# CESC16_copy.net
KiCad netlist of a schematic drawn in EasyEDA
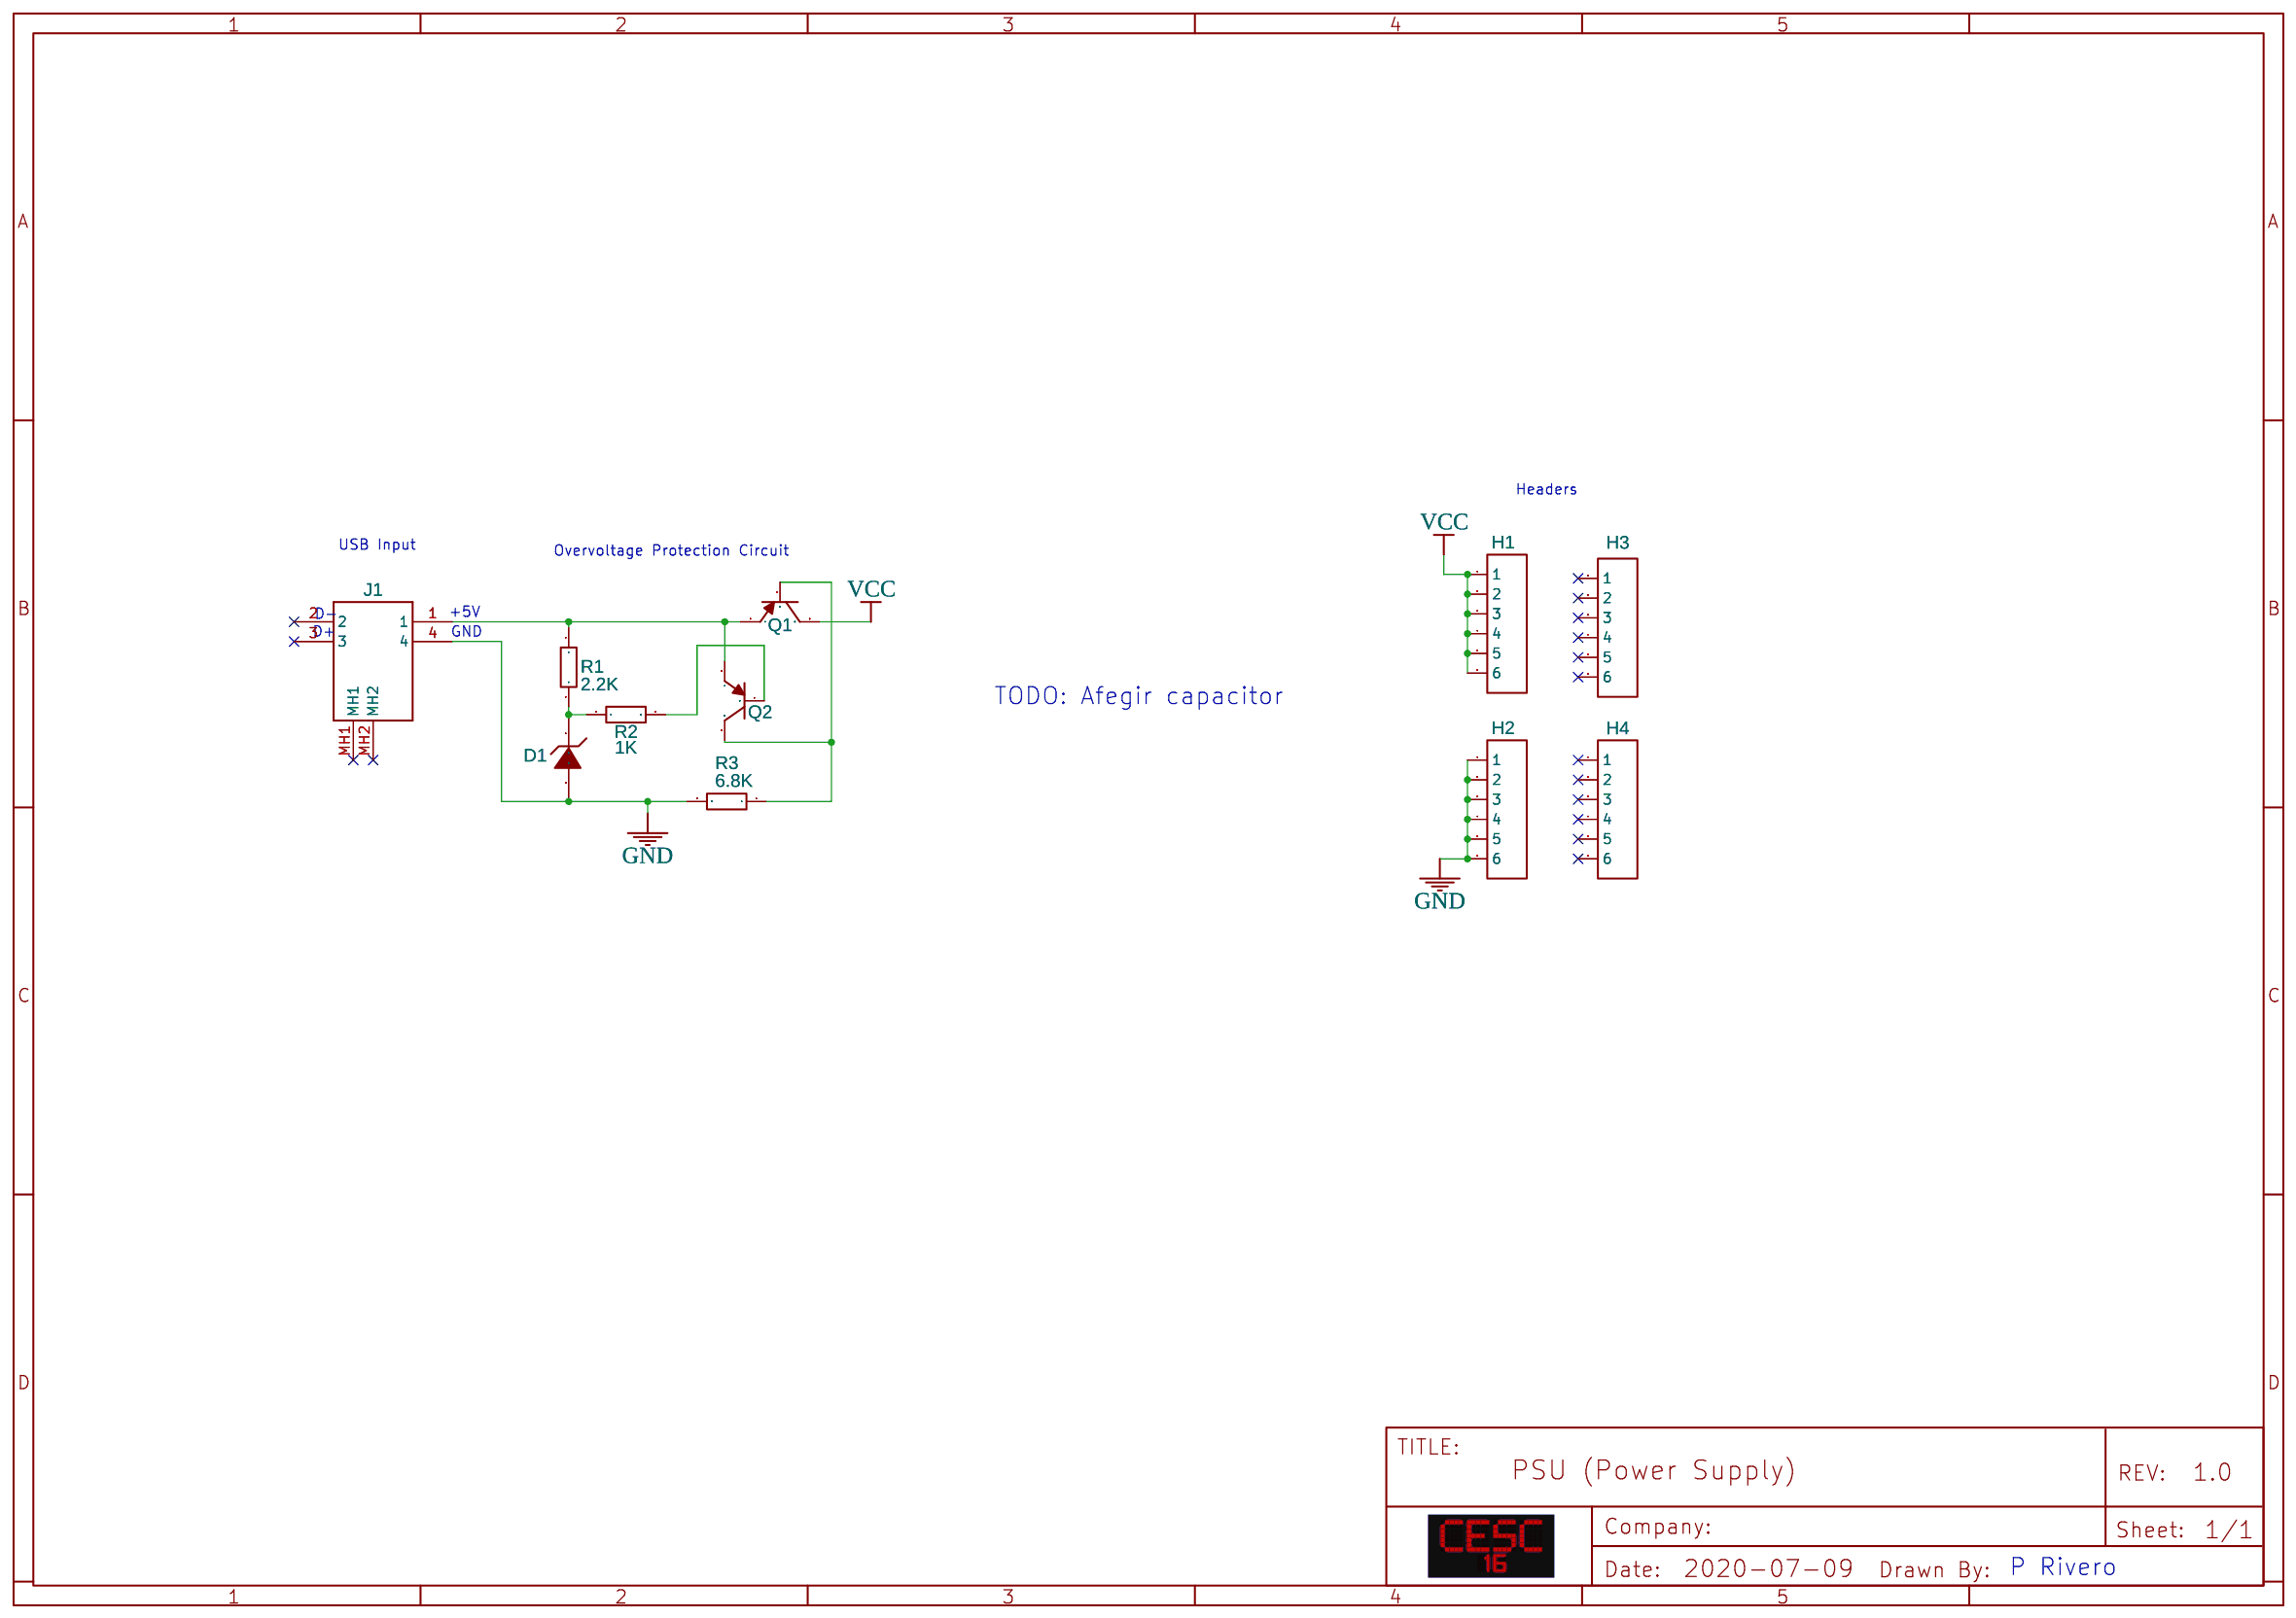
[diagram p0: PSU]
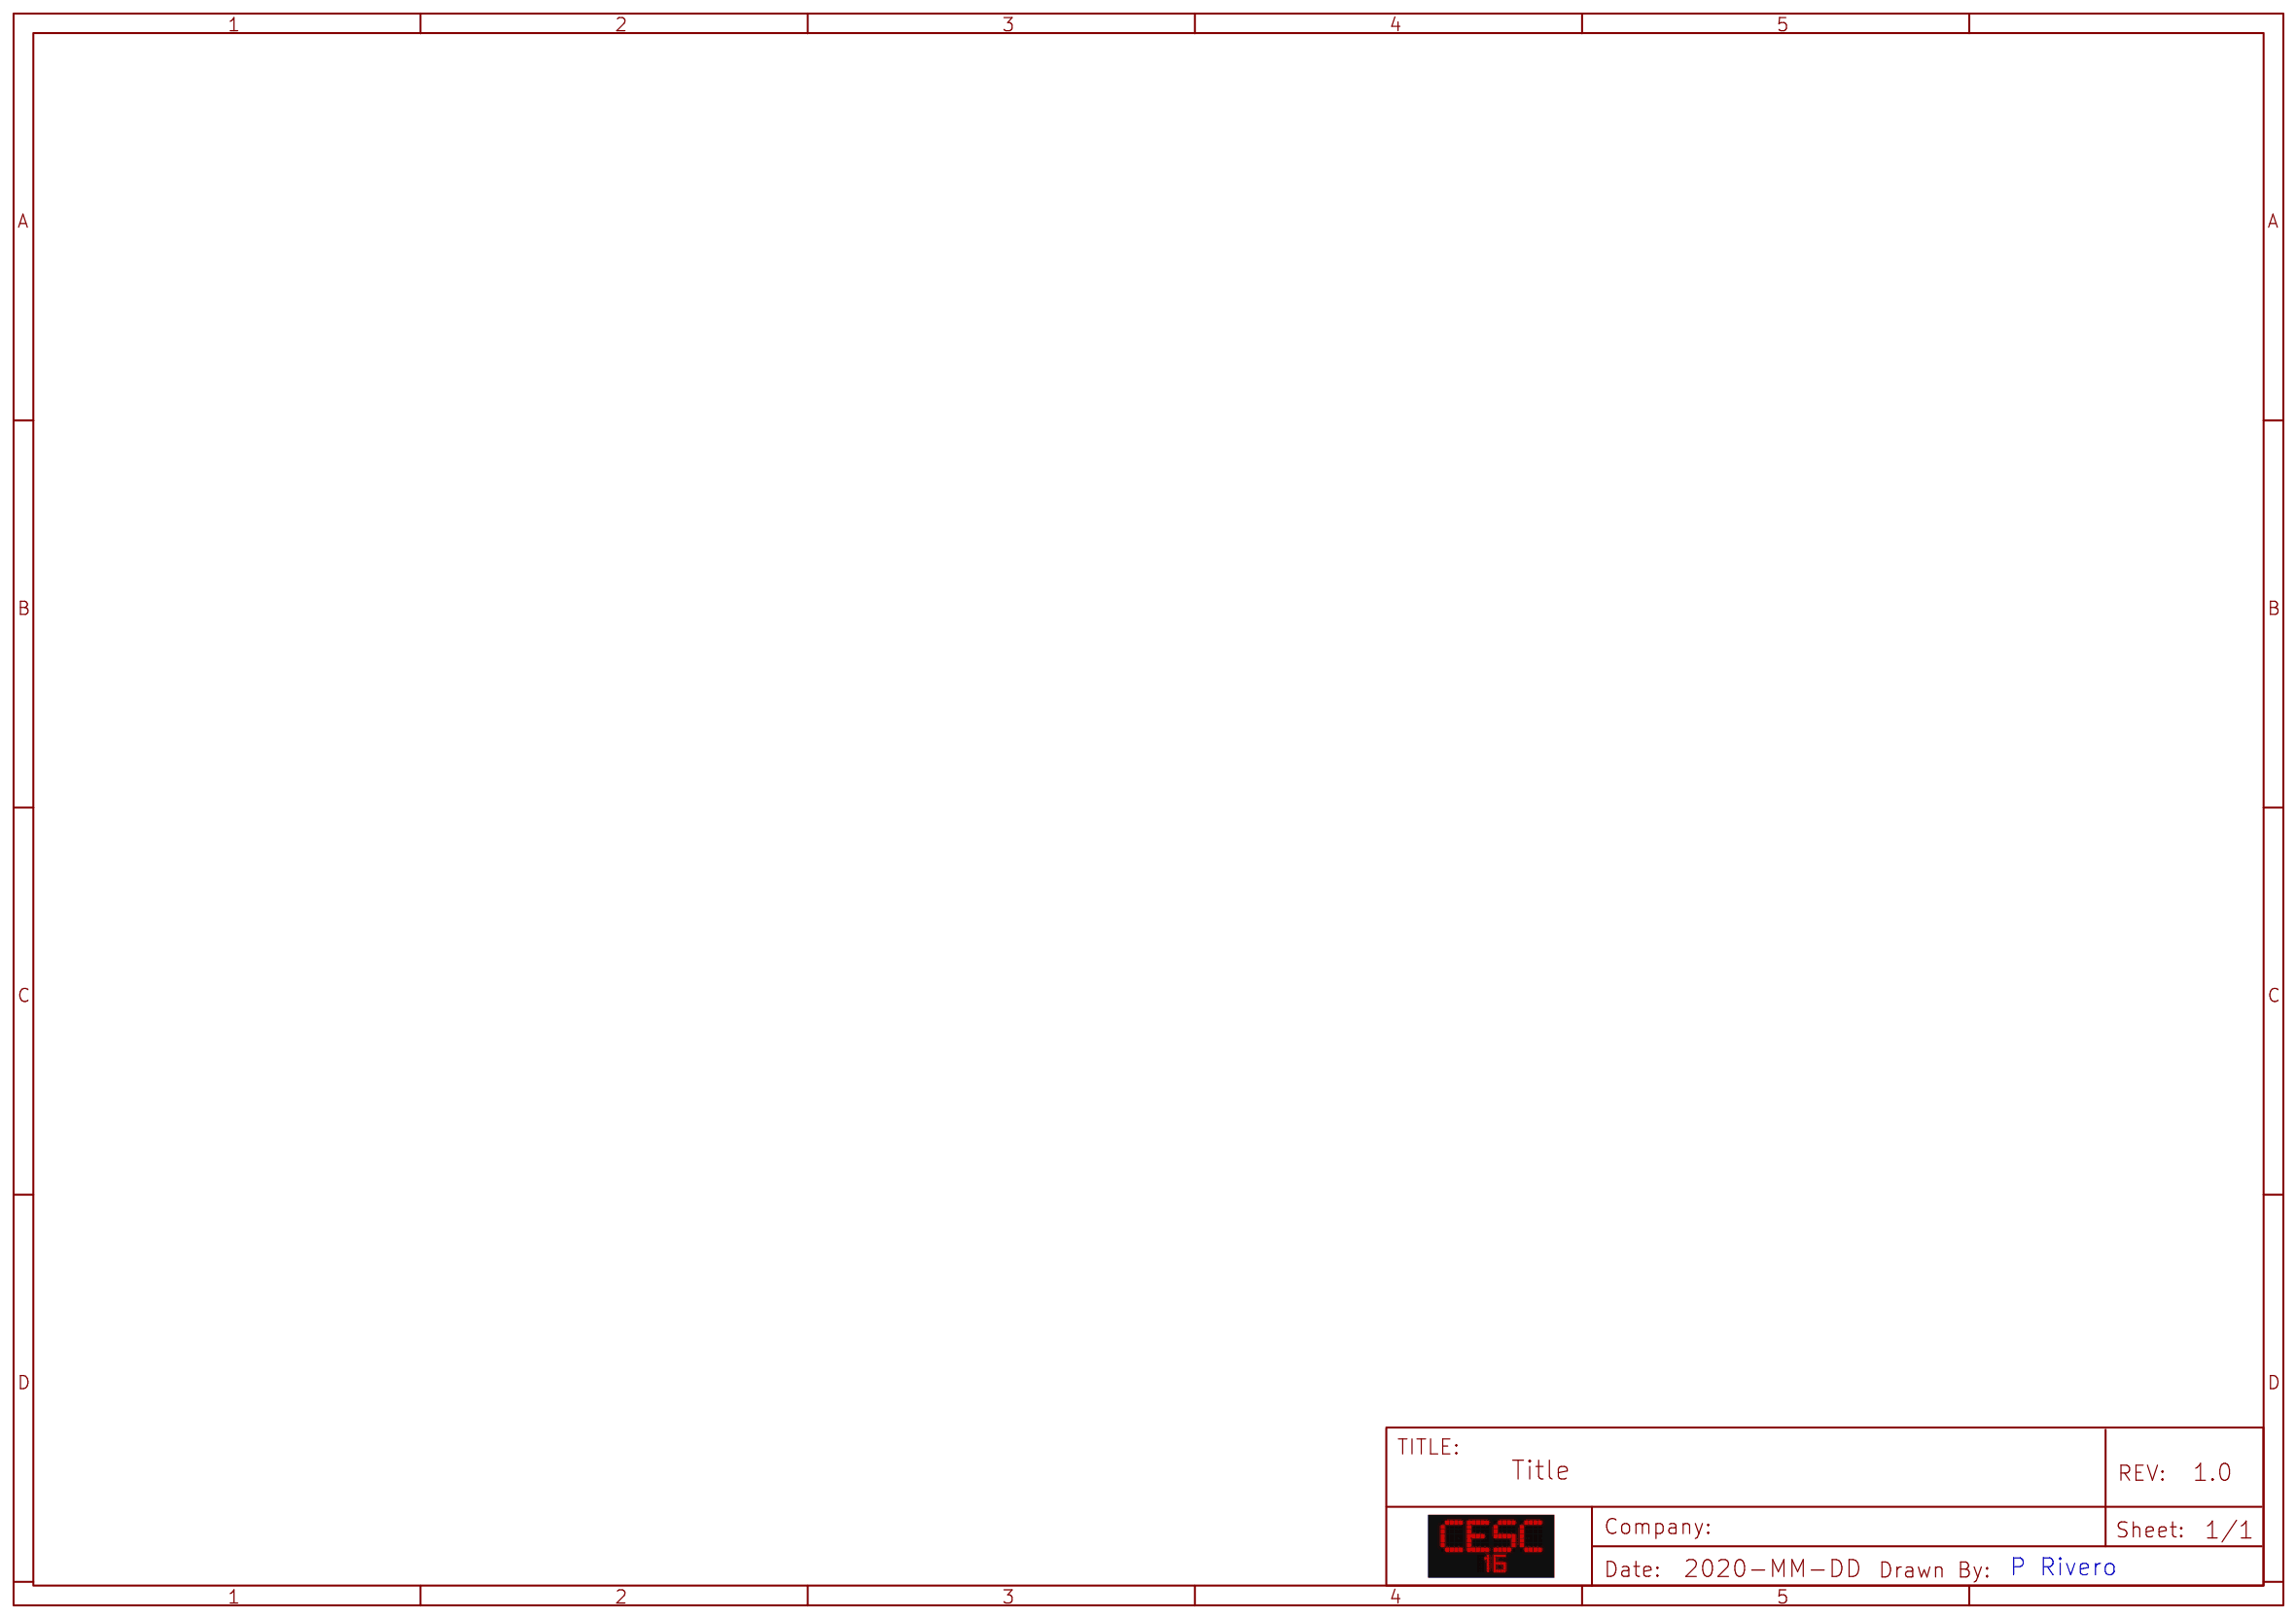
[diagram p1: _Template]
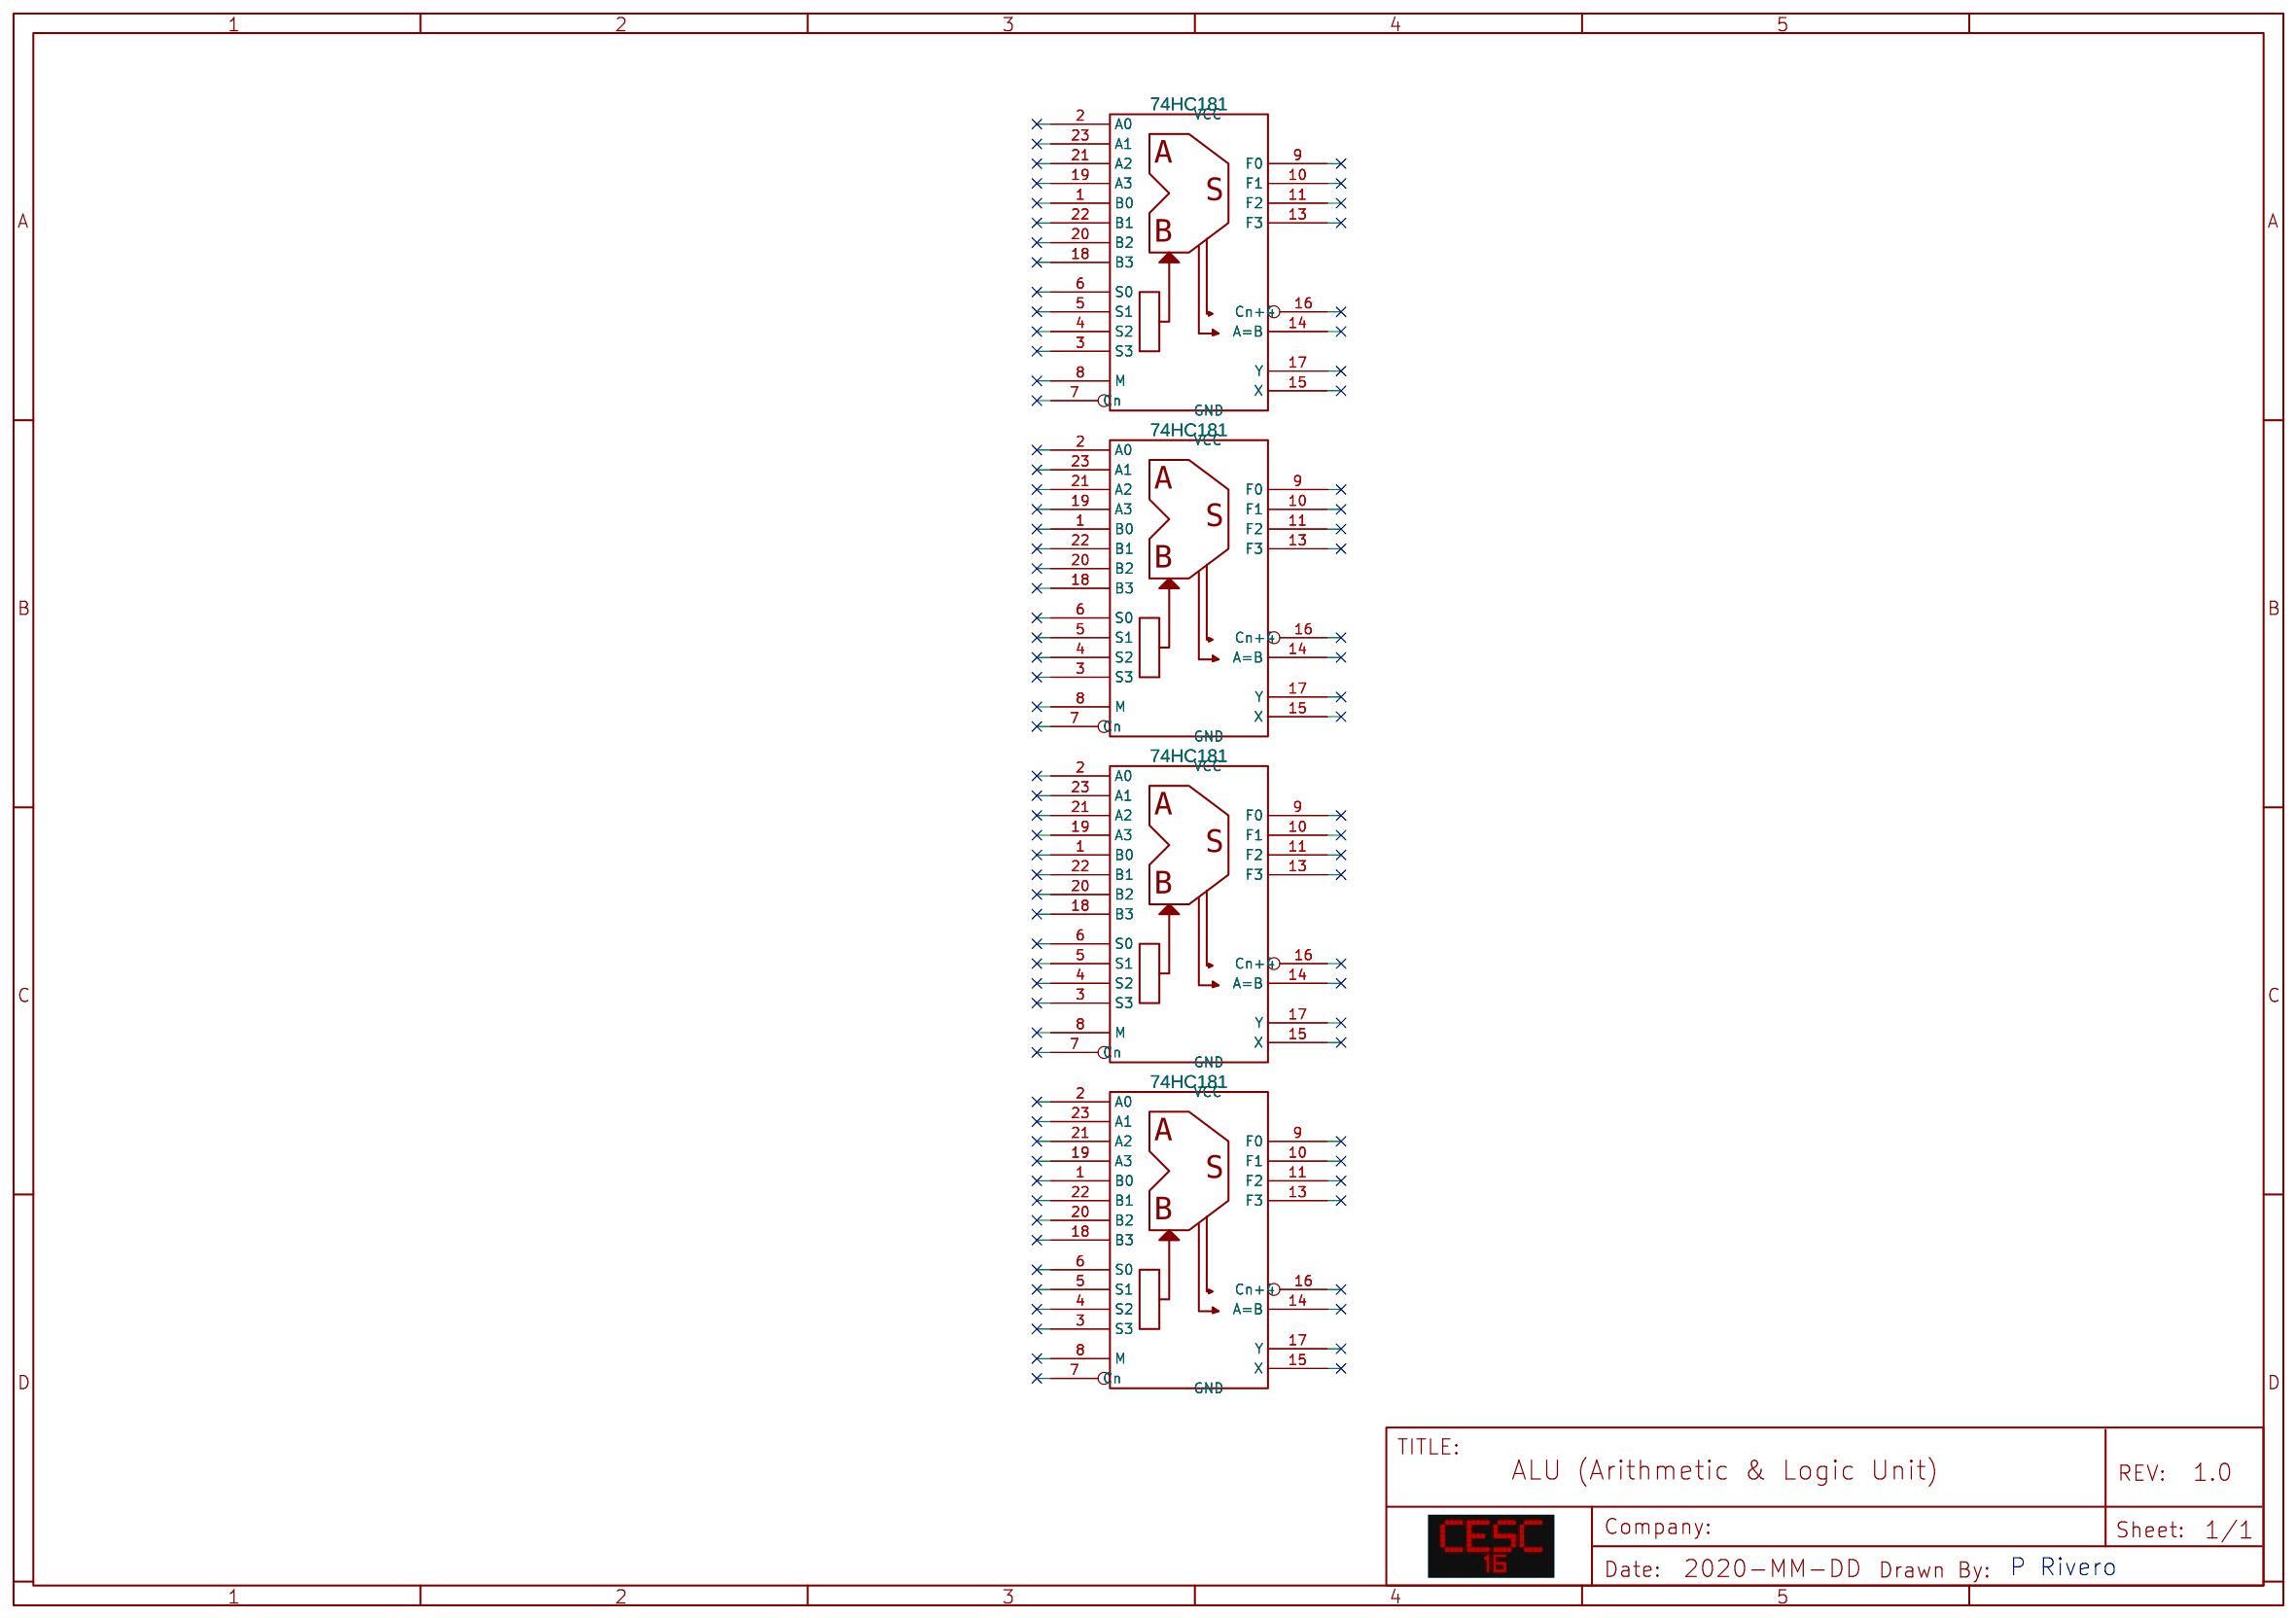
[diagram p2: ALU]
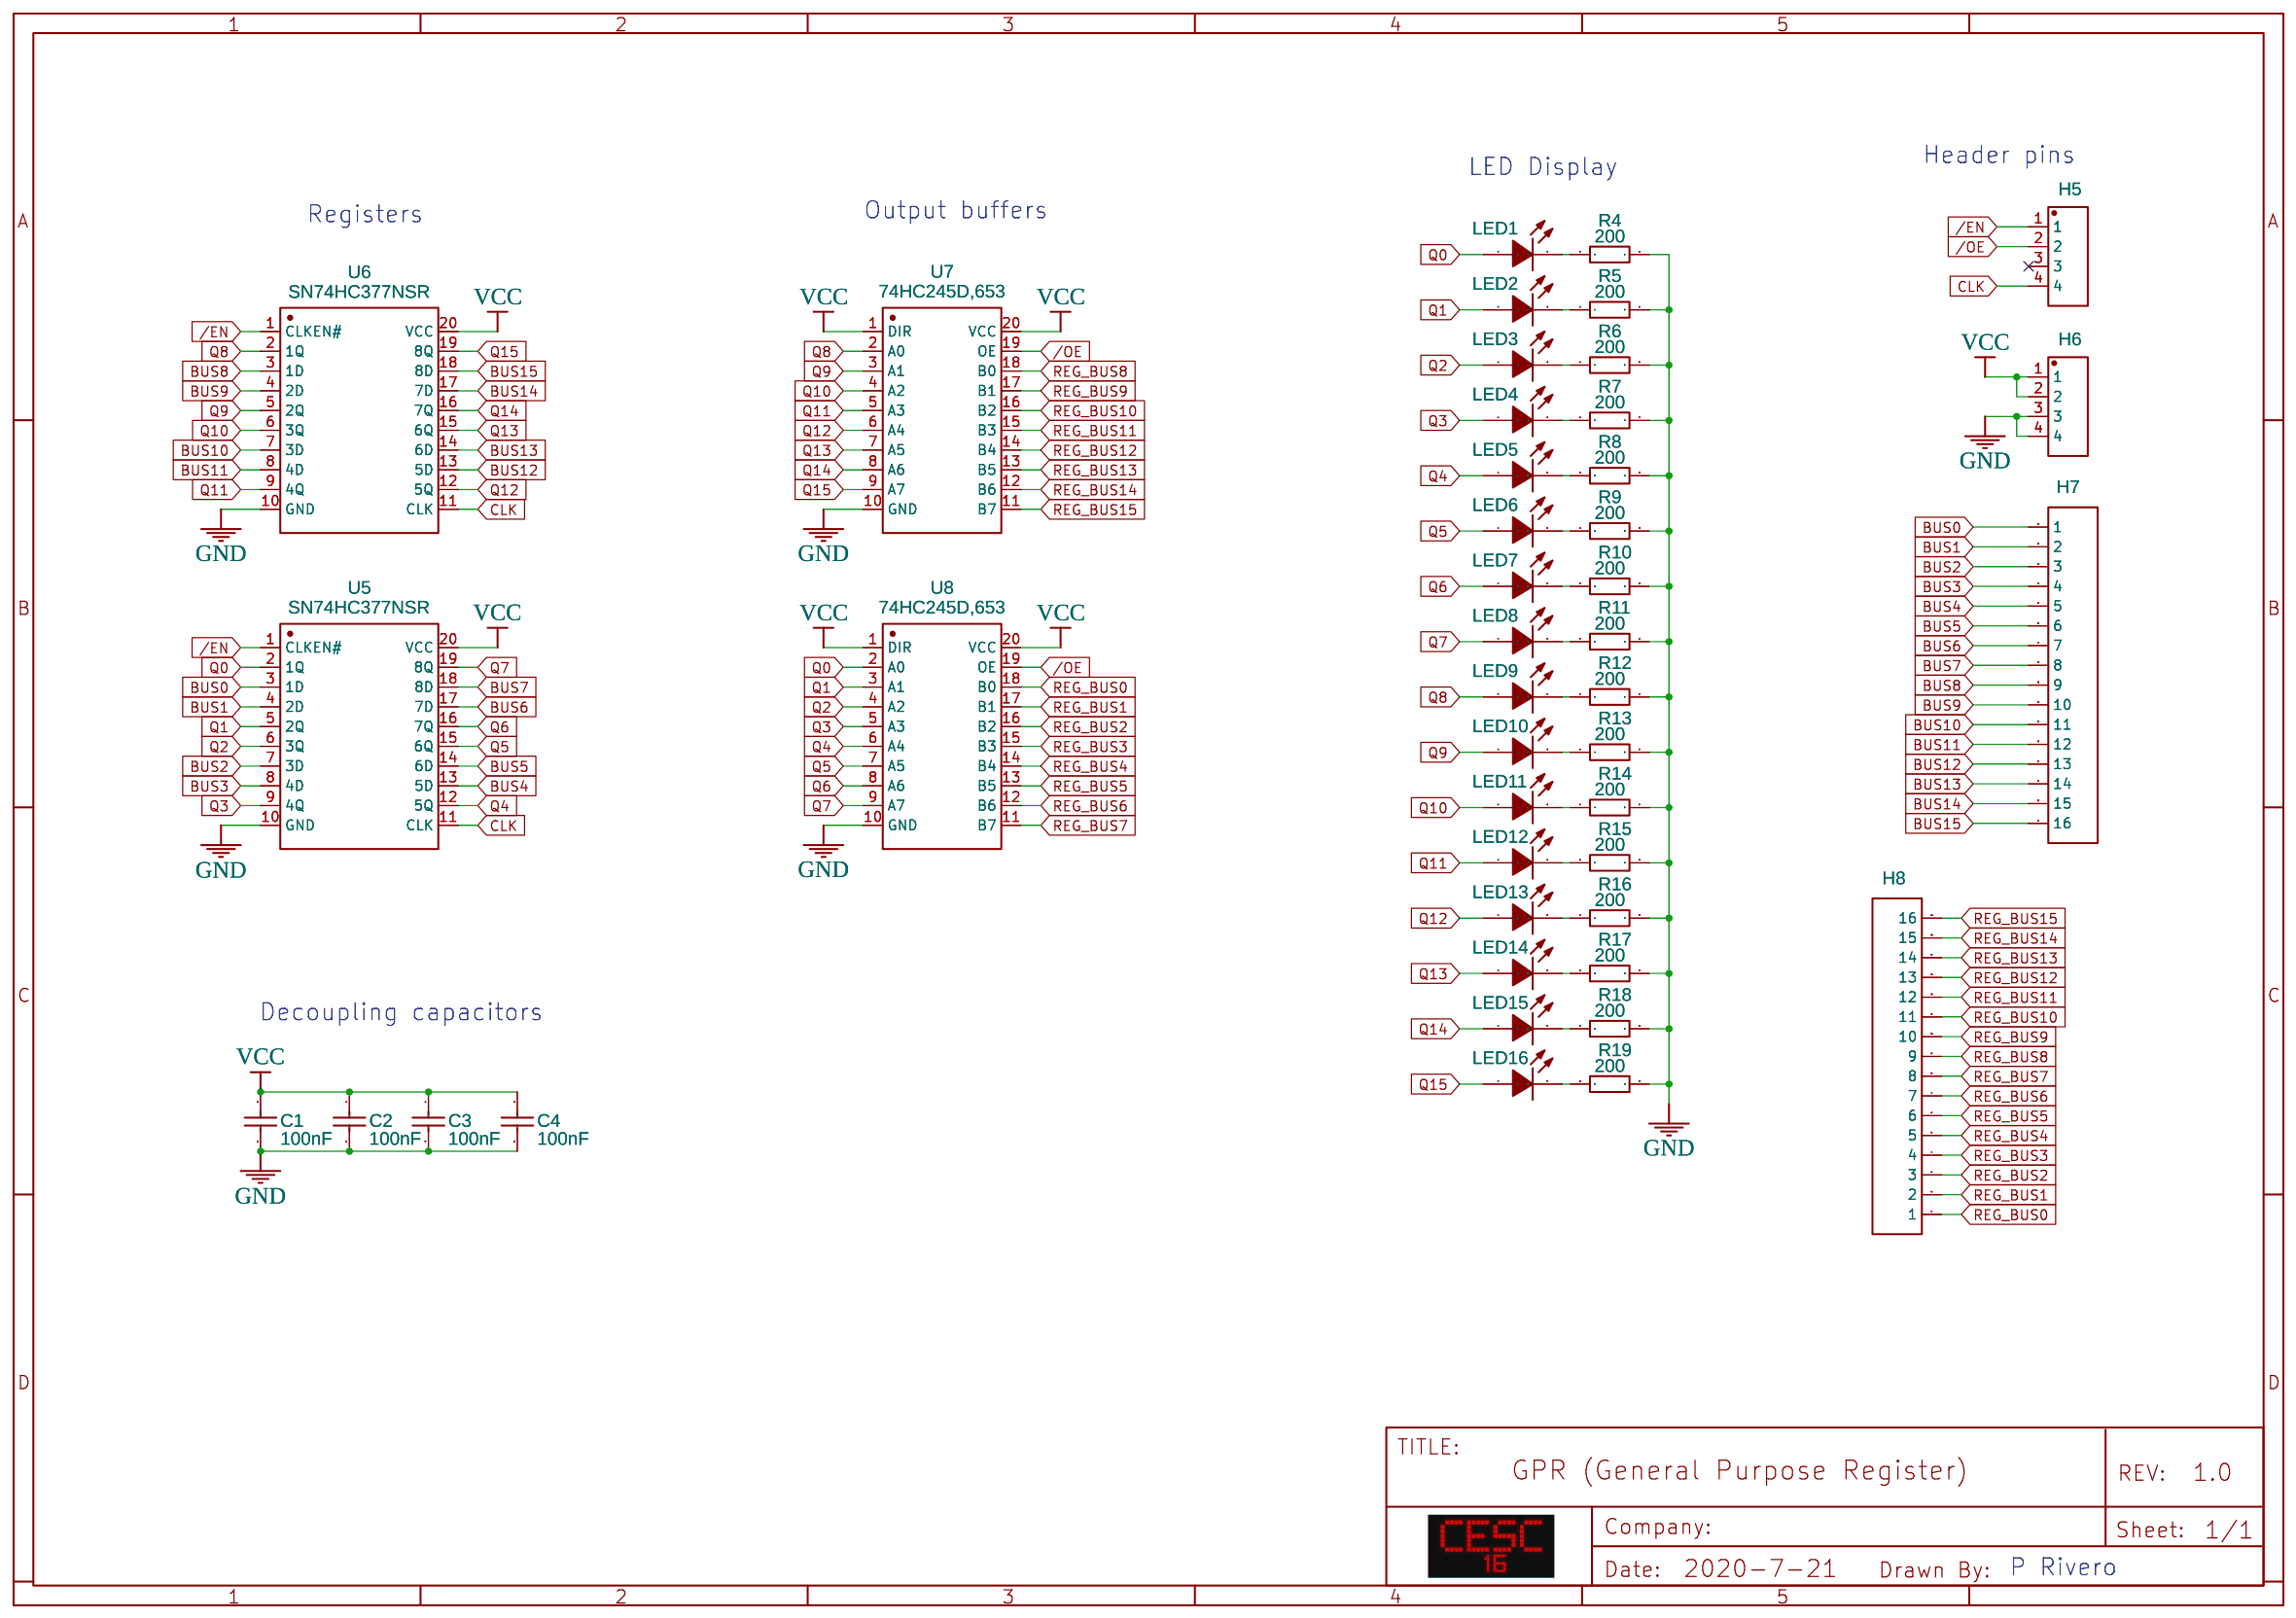
[diagram p3: GPR]

(export (version "E")
  (design (tool "Eeschema 10.0.6"))
  (components
    (comp (ref "D1")
      (value "ZMM5V6")
      (fields (field (name "BOM_Supplier Part") "C8062"))
      (libsource (lib "") (part "ZMM5V6"))
    )
    (comp (ref "H1")
      (value "Header-Male-2.54_1x6")
      (fields (field (name "BOM_Supplier Part") "C37208"))
      (libsource (lib "") (part "Header-Male-2.54_1x6"))
    )
    (comp (ref "H2")
      (value "Header-Male-2.54_1x6")
      (fields (field (name "BOM_Supplier Part") "C37208"))
      (libsource (lib "") (part "Header-Male-2.54_1x6"))
    )
    (comp (ref "H3")
      (value "Header-Male-2.54_1x6")
      (fields (field (name "BOM_Supplier Part") "C37208"))
      (libsource (lib "") (part "Header-Male-2.54_1x6"))
    )
    (comp (ref "H4")
      (value "Header-Male-2.54_1x6")
      (fields (field (name "BOM_Supplier Part") "C37208"))
      (libsource (lib "") (part "Header-Male-2.54_1x6"))
    )
    (comp (ref "J1") (value "UJ2-BH-1-TH") (libsource (lib "") (part "UJ2-BH-1-TH")))
    (comp (ref "Q1")
      (value "S9012 2T1")
      (fields (field (name "BOM_Supplier Part") "C8543"))
      (libsource (lib "") (part "S9012 2T1"))
    )
    (comp (ref "Q2")
      (value "S9012 2T1")
      (fields (field (name "BOM_Supplier Part") "C8543"))
      (libsource (lib "") (part "S9012 2T1_1"))
    )
    (comp (ref "R1")
      (value "2.2K")
      (fields
        (field (name "BOM_Manufacturer Part") "0603WAF2201T5E")
        (field (name "BOM_Supplier Part") "C4190")
      )
      (libsource (lib "") (part "0603WAF2201T5E"))
    )
    (comp (ref "R2")
      (value "1K")
      (fields
        (field (name "BOM_Manufacturer Part") "0402WGF1001TCE")
        (field (name "BOM_Supplier Part") "C11702")
      )
      (libsource (lib "") (part "0402WGF1001TCE"))
    )
    (comp (ref "R3")
      (value "6.8K")
      (fields
        (field (name "BOM_Manufacturer Part") "0402WGF6801TCE")
        (field (name "BOM_Supplier Part") "C25917")
      )
      (libsource (lib "") (part "0402WGF6801TCE"))
    )
    (comp (ref "U1") (value "74HC181") (libsource (lib "") (part "74LS181")))
    (comp (ref "U2") (value "74HC181") (libsource (lib "") (part "74LS181")))
    (comp (ref "U3") (value "74HC181") (libsource (lib "") (part "74LS181")))
    (comp (ref "U4") (value "74HC181") (libsource (lib "") (part "74LS181")))
    (comp (ref "C1")
      (value "100nF")
      (fields
        (field (name "BOM_Manufacturer Part") "CL05B104KO5NNNC")
        (field (name "BOM_Supplier Part") "C1525")
      )
      (libsource (lib "") (part "CL05B104KO5NNNC"))
    )
    (comp (ref "C2")
      (value "100nF")
      (fields
        (field (name "BOM_Manufacturer Part") "CL05B104KO5NNNC")
        (field (name "BOM_Supplier Part") "C1525")
      )
      (libsource (lib "") (part "CL05B104KO5NNNC"))
    )
    (comp (ref "C3")
      (value "100nF")
      (fields
        (field (name "BOM_Manufacturer Part") "CL05B104KO5NNNC")
        (field (name "BOM_Supplier Part") "C1525")
      )
      (libsource (lib "") (part "CL05B104KO5NNNC"))
    )
    (comp (ref "C4")
      (value "100nF")
      (fields
        (field (name "BOM_Manufacturer Part") "CL05B104KO5NNNC")
        (field (name "BOM_Supplier Part") "C1525")
      )
      (libsource (lib "") (part "CL05B104KO5NNNC"))
    )
    (comp (ref "H5")
      (value "Header-Male-2.54_1x4_C59481")
      (fields
        (field (name "BOM_Manufacturer Part") "Headers  Pins 1*4P")
        (field (name "BOM_Supplier Part") "C59481")
      )
      (libsource (lib "") (part "Header-Male-2.54_1x4_C59481"))
    )
    (comp (ref "H6")
      (value "Header-Male-2.54_1x4_C59481")
      (fields
        (field (name "BOM_Manufacturer Part") "Headers  Pins 1*4P")
        (field (name "BOM_Supplier Part") "C59481")
      )
      (libsource (lib "") (part "Header-Male-2.54_1x4_C59481"))
    )
    (comp (ref "H7")
      (value "Header-Female-2.54_1x16")
      (fields
        (field (name "BOM_Manufacturer Part") "Female header1*16P pitch 2.54mm")
        (field (name "BOM_Supplier Part") "C66987")
      )
      (libsource (lib "") (part "Header-Female-2.54_1x16_1"))
    )
    (comp (ref "H8")
      (value "Header-Female-2.54_1x16")
      (fields
        (field (name "BOM_Manufacturer Part") "Female header1*16P pitch 2.54mm")
        (field (name "BOM_Supplier Part") "C66987")
      )
      (libsource (lib "") (part "Header-Female-2.54_1x16"))
    )
    (comp (ref "LED1")
      (value "KT-0603R")
      (fields (field (name "BOM_Supplier Part") "C2286"))
      (libsource (lib "") (part "KT-0603R"))
    )
    (comp (ref "LED2")
      (value "KT-0603R")
      (fields (field (name "BOM_Supplier Part") "C2286"))
      (libsource (lib "") (part "KT-0603R"))
    )
    (comp (ref "LED3")
      (value "KT-0603R")
      (fields (field (name "BOM_Supplier Part") "C2286"))
      (libsource (lib "") (part "KT-0603R"))
    )
    (comp (ref "LED4")
      (value "KT-0603R")
      (fields (field (name "BOM_Supplier Part") "C2286"))
      (libsource (lib "") (part "KT-0603R"))
    )
    (comp (ref "LED5")
      (value "KT-0603R")
      (fields (field (name "BOM_Supplier Part") "C2286"))
      (libsource (lib "") (part "KT-0603R"))
    )
    (comp (ref "LED6")
      (value "KT-0603R")
      (fields (field (name "BOM_Supplier Part") "C2286"))
      (libsource (lib "") (part "KT-0603R"))
    )
    (comp (ref "LED7")
      (value "KT-0603R")
      (fields (field (name "BOM_Supplier Part") "C2286"))
      (libsource (lib "") (part "KT-0603R"))
    )
    (comp (ref "LED8")
      (value "KT-0603R")
      (fields (field (name "BOM_Supplier Part") "C2286"))
      (libsource (lib "") (part "KT-0603R"))
    )
    (comp (ref "LED9")
      (value "KT-0603R")
      (fields (field (name "BOM_Supplier Part") "C2286"))
      (libsource (lib "") (part "KT-0603R"))
    )
    (comp (ref "LED10")
      (value "KT-0603R")
      (fields (field (name "BOM_Supplier Part") "C2286"))
      (libsource (lib "") (part "KT-0603R"))
    )
    (comp (ref "LED11")
      (value "KT-0603R")
      (fields (field (name "BOM_Supplier Part") "C2286"))
      (libsource (lib "") (part "KT-0603R"))
    )
    (comp (ref "LED12")
      (value "KT-0603R")
      (fields (field (name "BOM_Supplier Part") "C2286"))
      (libsource (lib "") (part "KT-0603R"))
    )
    (comp (ref "LED13")
      (value "KT-0603R")
      (fields (field (name "BOM_Supplier Part") "C2286"))
      (libsource (lib "") (part "KT-0603R"))
    )
    (comp (ref "LED14")
      (value "KT-0603R")
      (fields (field (name "BOM_Supplier Part") "C2286"))
      (libsource (lib "") (part "KT-0603R"))
    )
    (comp (ref "LED15")
      (value "KT-0603R")
      (fields (field (name "BOM_Supplier Part") "C2286"))
      (libsource (lib "") (part "KT-0603R"))
    )
    (comp (ref "LED16")
      (value "KT-0603R")
      (fields (field (name "BOM_Supplier Part") "C2286"))
      (libsource (lib "") (part "KT-0603R"))
    )
    (comp (ref "R4")
      (value "200")
      (fields
        (field (name "BOM_Manufacturer Part") "0603WAF2000T5E")
        (field (name "BOM_Supplier Part") "C8218")
      )
      (libsource (lib "") (part "0603WAF2000T5E"))
    )
    (comp (ref "R5")
      (value "200")
      (fields
        (field (name "BOM_Manufacturer Part") "0603WAF2000T5E")
        (field (name "BOM_Supplier Part") "C8218")
      )
      (libsource (lib "") (part "0603WAF2000T5E"))
    )
    (comp (ref "R6")
      (value "200")
      (fields
        (field (name "BOM_Manufacturer Part") "0603WAF2000T5E")
        (field (name "BOM_Supplier Part") "C8218")
      )
      (libsource (lib "") (part "0603WAF2000T5E"))
    )
    (comp (ref "R7")
      (value "200")
      (fields
        (field (name "BOM_Manufacturer Part") "0603WAF2000T5E")
        (field (name "BOM_Supplier Part") "C8218")
      )
      (libsource (lib "") (part "0603WAF2000T5E"))
    )
    (comp (ref "R8")
      (value "200")
      (fields
        (field (name "BOM_Manufacturer Part") "0603WAF2000T5E")
        (field (name "BOM_Supplier Part") "C8218")
      )
      (libsource (lib "") (part "0603WAF2000T5E"))
    )
    (comp (ref "R9")
      (value "200")
      (fields
        (field (name "BOM_Manufacturer Part") "0603WAF2000T5E")
        (field (name "BOM_Supplier Part") "C8218")
      )
      (libsource (lib "") (part "0603WAF2000T5E"))
    )
    (comp (ref "R10")
      (value "200")
      (fields
        (field (name "BOM_Manufacturer Part") "0603WAF2000T5E")
        (field (name "BOM_Supplier Part") "C8218")
      )
      (libsource (lib "") (part "0603WAF2000T5E"))
    )
    (comp (ref "R11")
      (value "200")
      (fields
        (field (name "BOM_Manufacturer Part") "0603WAF2000T5E")
        (field (name "BOM_Supplier Part") "C8218")
      )
      (libsource (lib "") (part "0603WAF2000T5E"))
    )
    (comp (ref "R12")
      (value "200")
      (fields
        (field (name "BOM_Manufacturer Part") "0603WAF2000T5E")
        (field (name "BOM_Supplier Part") "C8218")
      )
      (libsource (lib "") (part "0603WAF2000T5E"))
    )
    (comp (ref "R13")
      (value "200")
      (fields
        (field (name "BOM_Manufacturer Part") "0603WAF2000T5E")
        (field (name "BOM_Supplier Part") "C8218")
      )
      (libsource (lib "") (part "0603WAF2000T5E"))
    )
    (comp (ref "R14")
      (value "200")
      (fields
        (field (name "BOM_Manufacturer Part") "0603WAF2000T5E")
        (field (name "BOM_Supplier Part") "C8218")
      )
      (libsource (lib "") (part "0603WAF2000T5E"))
    )
    (comp (ref "R15")
      (value "200")
      (fields
        (field (name "BOM_Manufacturer Part") "0603WAF2000T5E")
        (field (name "BOM_Supplier Part") "C8218")
      )
      (libsource (lib "") (part "0603WAF2000T5E"))
    )
    (comp (ref "R16")
      (value "200")
      (fields
        (field (name "BOM_Manufacturer Part") "0603WAF2000T5E")
        (field (name "BOM_Supplier Part") "C8218")
      )
      (libsource (lib "") (part "0603WAF2000T5E"))
    )
    (comp (ref "R17")
      (value "200")
      (fields
        (field (name "BOM_Manufacturer Part") "0603WAF2000T5E")
        (field (name "BOM_Supplier Part") "C8218")
      )
      (libsource (lib "") (part "0603WAF2000T5E"))
    )
    (comp (ref "R18")
      (value "200")
      (fields
        (field (name "BOM_Manufacturer Part") "0603WAF2000T5E")
        (field (name "BOM_Supplier Part") "C8218")
      )
      (libsource (lib "") (part "0603WAF2000T5E"))
    )
    (comp (ref "R19")
      (value "200")
      (fields
        (field (name "BOM_Manufacturer Part") "0603WAF2000T5E")
        (field (name "BOM_Supplier Part") "C8218")
      )
      (libsource (lib "") (part "0603WAF2000T5E"))
    )
    (comp (ref "U5")
      (value "SN74HC377NSR")
      (fields (field (name "BOM_Supplier Part") "C7647"))
      (libsource (lib "") (part "SN74HC377NSR"))
    )
    (comp (ref "U6")
      (value "SN74HC377NSR")
      (fields (field (name "BOM_Supplier Part") "C7647"))
      (libsource (lib "") (part "SN74HC377NSR"))
    )
    (comp (ref "U7")
      (value "74HC245D,653")
      (fields (field (name "BOM_Supplier Part") "C5625"))
      (libsource (lib "") (part "74HC245D,653"))
    )
    (comp (ref "U8")
      (value "74HC245D,653")
      (fields (field (name "BOM_Supplier Part") "C5625"))
      (libsource (lib "") (part "74HC245D,653"))
    )
  )
  (nets
    (net (code "1") (name "BUS0") (class "Default")
      (node (ref "H7") (pin "1") (pinfunction "1_1") (pintype "input"))
      (node (ref "U5") (pin "3") (pinfunction "1D_3") (pintype "unspecified"))
    )
    (net (code "2") (name "BUS1") (class "Default")
      (node (ref "H7") (pin "2") (pinfunction "2_2") (pintype "input"))
      (node (ref "U5") (pin "4") (pinfunction "2D_4") (pintype "unspecified"))
    )
    (net (code "3") (name "BUS2") (class "Default")
      (node (ref "H7") (pin "3") (pinfunction "3_3") (pintype "input"))
      (node (ref "U5") (pin "7") (pinfunction "3D_7") (pintype "unspecified"))
    )
    (net (code "4") (name "BUS3") (class "Default")
      (node (ref "H7") (pin "4") (pinfunction "4_4") (pintype "input"))
      (node (ref "U5") (pin "8") (pinfunction "4D_8") (pintype "unspecified"))
    )
    (net (code "5") (name "BUS4") (class "Default")
      (node (ref "H7") (pin "5") (pinfunction "5_5") (pintype "input"))
      (node (ref "U5") (pin "13") (pinfunction "5D_13") (pintype "unspecified"))
    )
    (net (code "6") (name "BUS5") (class "Default")
      (node (ref "H7") (pin "6") (pinfunction "6_6") (pintype "input"))
      (node (ref "U5") (pin "14") (pinfunction "6D_14") (pintype "unspecified"))
    )
    (net (code "7") (name "BUS6") (class "Default")
      (node (ref "H7") (pin "7") (pinfunction "7_7") (pintype "input"))
      (node (ref "U5") (pin "17") (pinfunction "7D_17") (pintype "unspecified"))
    )
    (net (code "8") (name "BUS7") (class "Default")
      (node (ref "H7") (pin "8") (pinfunction "8_8") (pintype "input"))
      (node (ref "U5") (pin "18") (pinfunction "8D_18") (pintype "unspecified"))
    )
    (net (code "9") (name "BUS8") (class "Default")
      (node (ref "H7") (pin "9") (pinfunction "9_9") (pintype "input"))
      (node (ref "U6") (pin "3") (pinfunction "1D_3") (pintype "unspecified"))
    )
    (net (code "10") (name "BUS9") (class "Default")
      (node (ref "H7") (pin "10") (pinfunction "10_10") (pintype "input"))
      (node (ref "U6") (pin "4") (pinfunction "2D_4") (pintype "unspecified"))
    )
    (net (code "11") (name "BUS10") (class "Default")
      (node (ref "H7") (pin "11") (pinfunction "11_11") (pintype "input"))
      (node (ref "U6") (pin "7") (pinfunction "3D_7") (pintype "unspecified"))
    )
    (net (code "12") (name "BUS11") (class "Default")
      (node (ref "H7") (pin "12") (pinfunction "12_12") (pintype "input"))
      (node (ref "U6") (pin "8") (pinfunction "4D_8") (pintype "unspecified"))
    )
    (net (code "13") (name "BUS12") (class "Default")
      (node (ref "H7") (pin "13") (pinfunction "13_13") (pintype "input"))
      (node (ref "U6") (pin "13") (pinfunction "5D_13") (pintype "unspecified"))
    )
    (net (code "14") (name "BUS13") (class "Default")
      (node (ref "H7") (pin "14") (pinfunction "14_14") (pintype "input"))
      (node (ref "U6") (pin "14") (pinfunction "6D_14") (pintype "unspecified"))
    )
    (net (code "15") (name "BUS14") (class "Default")
      (node (ref "H7") (pin "15") (pinfunction "15_15") (pintype "input"))
      (node (ref "U6") (pin "17") (pinfunction "7D_17") (pintype "unspecified"))
    )
    (net (code "16") (name "BUS15") (class "Default")
      (node (ref "H7") (pin "16") (pinfunction "16_16") (pintype "input"))
      (node (ref "U6") (pin "18") (pinfunction "8D_18") (pintype "unspecified"))
    )
    (net (code "17") (name "CLK") (class "Default")
      (node (ref "H5") (pin "4") (pinfunction "4_4") (pintype "unspecified"))
      (node (ref "U5") (pin "11") (pinfunction "CLK_11") (pintype "unspecified"))
      (node (ref "U6") (pin "11") (pinfunction "CLK_11") (pintype "unspecified"))
    )
    (net (code "18") (name "GND") (class "Default")
      (node (ref "C1") (pin "2") (pinfunction "2_2") (pintype "input"))
      (node (ref "C2") (pin "2") (pinfunction "2_2") (pintype "input"))
      (node (ref "C3") (pin "2") (pinfunction "2_2") (pintype "input"))
      (node (ref "C4") (pin "2") (pinfunction "2_2") (pintype "input"))
      (node (ref "D1") (pin "2") (pinfunction "A_2") (pintype "unspecified"))
      (node (ref "H2") (pin "1") (pinfunction "1_1") (pintype "input"))
      (node (ref "H2") (pin "2") (pinfunction "2_2") (pintype "input"))
      (node (ref "H2") (pin "3") (pinfunction "3_3") (pintype "input"))
      (node (ref "H2") (pin "4") (pinfunction "4_4") (pintype "input"))
      (node (ref "H2") (pin "5") (pinfunction "5_5") (pintype "input"))
      (node (ref "H2") (pin "6") (pinfunction "6_6") (pintype "input"))
      (node (ref "H6") (pin "3") (pinfunction "3_3") (pintype "unspecified"))
      (node (ref "H6") (pin "4") (pinfunction "4_4") (pintype "unspecified"))
      (node (ref "J1") (pin "4") (pinfunction "4_4") (pintype "bidirectional"))
      (node (ref "R10") (pin "2") (pinfunction "2_2") (pintype "input"))
      (node (ref "R11") (pin "2") (pinfunction "2_2") (pintype "input"))
      (node (ref "R12") (pin "2") (pinfunction "2_2") (pintype "input"))
      (node (ref "R13") (pin "2") (pinfunction "2_2") (pintype "input"))
      (node (ref "R14") (pin "2") (pinfunction "2_2") (pintype "input"))
      (node (ref "R15") (pin "2") (pinfunction "2_2") (pintype "input"))
      (node (ref "R16") (pin "2") (pinfunction "2_2") (pintype "input"))
      (node (ref "R17") (pin "2") (pinfunction "2_2") (pintype "input"))
      (node (ref "R18") (pin "2") (pinfunction "2_2") (pintype "input"))
      (node (ref "R19") (pin "2") (pinfunction "2_2") (pintype "input"))
      (node (ref "R3") (pin "2") (pinfunction "2_2") (pintype "input"))
      (node (ref "R4") (pin "2") (pinfunction "2_2") (pintype "input"))
      (node (ref "R5") (pin "2") (pinfunction "2_2") (pintype "input"))
      (node (ref "R6") (pin "2") (pinfunction "2_2") (pintype "input"))
      (node (ref "R7") (pin "2") (pinfunction "2_2") (pintype "input"))
      (node (ref "R8") (pin "2") (pinfunction "2_2") (pintype "input"))
      (node (ref "R9") (pin "2") (pinfunction "2_2") (pintype "input"))
      (node (ref "U5") (pin "10") (pinfunction "GND_10") (pintype "unspecified"))
      (node (ref "U6") (pin "10") (pinfunction "GND_10") (pintype "unspecified"))
      (node (ref "U7") (pin "10") (pinfunction "GND_10") (pintype "unspecified"))
      (node (ref "U8") (pin "10") (pinfunction "GND_10") (pintype "unspecified"))
    )
    (net (code "19") (name "Net-(D1-C)") (class "Default")
      (node (ref "D1") (pin "1") (pinfunction "C_1") (pintype "unspecified"))
      (node (ref "R1") (pin "2") (pinfunction "2_2") (pintype "input"))
      (node (ref "R2") (pin "1") (pinfunction "1_1") (pintype "input"))
    )
    (net (code "20") (name "Net-(LED1-K)") (class "Default")
      (node (ref "LED1") (pin "2") (pinfunction "K_2") (pintype "unspecified"))
      (node (ref "R4") (pin "1") (pinfunction "1_1") (pintype "input"))
    )
    (net (code "21") (name "Net-(LED2-K)") (class "Default")
      (node (ref "LED2") (pin "2") (pinfunction "K_2") (pintype "unspecified"))
      (node (ref "R5") (pin "1") (pinfunction "1_1") (pintype "input"))
    )
    (net (code "22") (name "Net-(LED3-K)") (class "Default")
      (node (ref "LED3") (pin "2") (pinfunction "K_2") (pintype "unspecified"))
      (node (ref "R6") (pin "1") (pinfunction "1_1") (pintype "input"))
    )
    (net (code "23") (name "Net-(LED4-K)") (class "Default")
      (node (ref "LED4") (pin "2") (pinfunction "K_2") (pintype "unspecified"))
      (node (ref "R7") (pin "1") (pinfunction "1_1") (pintype "input"))
    )
    (net (code "24") (name "Net-(LED5-K)") (class "Default")
      (node (ref "LED5") (pin "2") (pinfunction "K_2") (pintype "unspecified"))
      (node (ref "R8") (pin "1") (pinfunction "1_1") (pintype "input"))
    )
    (net (code "25") (name "Net-(LED6-K)") (class "Default")
      (node (ref "LED6") (pin "2") (pinfunction "K_2") (pintype "unspecified"))
      (node (ref "R9") (pin "1") (pinfunction "1_1") (pintype "input"))
    )
    (net (code "26") (name "Net-(LED7-K)") (class "Default")
      (node (ref "LED7") (pin "2") (pinfunction "K_2") (pintype "unspecified"))
      (node (ref "R10") (pin "1") (pinfunction "1_1") (pintype "input"))
    )
    (net (code "27") (name "Net-(LED8-K)") (class "Default")
      (node (ref "LED8") (pin "2") (pinfunction "K_2") (pintype "unspecified"))
      (node (ref "R11") (pin "1") (pinfunction "1_1") (pintype "input"))
    )
    (net (code "28") (name "Net-(LED9-K)") (class "Default")
      (node (ref "LED9") (pin "2") (pinfunction "K_2") (pintype "unspecified"))
      (node (ref "R12") (pin "1") (pinfunction "1_1") (pintype "input"))
    )
    (net (code "29") (name "Net-(LED10-K)") (class "Default")
      (node (ref "LED10") (pin "2") (pinfunction "K_2") (pintype "unspecified"))
      (node (ref "R13") (pin "1") (pinfunction "1_1") (pintype "input"))
    )
    (net (code "30") (name "Net-(LED11-K)") (class "Default")
      (node (ref "LED11") (pin "2") (pinfunction "K_2") (pintype "unspecified"))
      (node (ref "R14") (pin "1") (pinfunction "1_1") (pintype "input"))
    )
    (net (code "31") (name "Net-(LED12-K)") (class "Default")
      (node (ref "LED12") (pin "2") (pinfunction "K_2") (pintype "unspecified"))
      (node (ref "R15") (pin "1") (pinfunction "1_1") (pintype "input"))
    )
    (net (code "32") (name "Net-(LED13-K)") (class "Default")
      (node (ref "LED13") (pin "2") (pinfunction "K_2") (pintype "unspecified"))
      (node (ref "R16") (pin "1") (pinfunction "1_1") (pintype "input"))
    )
    (net (code "33") (name "Net-(LED14-K)") (class "Default")
      (node (ref "LED14") (pin "2") (pinfunction "K_2") (pintype "unspecified"))
      (node (ref "R17") (pin "1") (pinfunction "1_1") (pintype "input"))
    )
    (net (code "34") (name "Net-(LED15-K)") (class "Default")
      (node (ref "LED15") (pin "2") (pinfunction "K_2") (pintype "unspecified"))
      (node (ref "R18") (pin "1") (pinfunction "1_1") (pintype "input"))
    )
    (net (code "35") (name "Net-(LED16-K)") (class "Default")
      (node (ref "LED16") (pin "2") (pinfunction "K_2") (pintype "unspecified"))
      (node (ref "R19") (pin "1") (pinfunction "1_1") (pintype "input"))
    )
    (net (code "36") (name "Net-(Q1-B)") (class "Default")
      (node (ref "Q1") (pin "1") (pinfunction "B_1") (pintype "unspecified"))
      (node (ref "Q2") (pin "3") (pinfunction "C_3") (pintype "unspecified"))
      (node (ref "R3") (pin "1") (pinfunction "1_1") (pintype "input"))
    )
    (net (code "37") (name "Net-(Q1-E)") (class "Default")
      (node (ref "J1") (pin "1") (pinfunction "1_1") (pintype "bidirectional"))
      (node (ref "Q1") (pin "2") (pinfunction "E_2") (pintype "unspecified"))
      (node (ref "Q2") (pin "2") (pinfunction "E_2") (pintype "unspecified"))
      (node (ref "R1") (pin "1") (pinfunction "1_1") (pintype "input"))
    )
    (net (code "38") (name "Net-(Q2-B)") (class "Default")
      (node (ref "Q2") (pin "1") (pinfunction "B_1") (pintype "unspecified"))
      (node (ref "R2") (pin "2") (pinfunction "2_2") (pintype "input"))
    )
    (net (code "39") (name "Q0") (class "Default")
      (node (ref "LED1") (pin "1") (pinfunction "A_1") (pintype "unspecified"))
      (node (ref "U5") (pin "2") (pinfunction "1Q_2") (pintype "unspecified"))
      (node (ref "U8") (pin "2") (pinfunction "A0_2") (pintype "unspecified"))
    )
    (net (code "40") (name "Q1") (class "Default")
      (node (ref "LED2") (pin "1") (pinfunction "A_1") (pintype "unspecified"))
      (node (ref "U5") (pin "5") (pinfunction "2Q_5") (pintype "unspecified"))
      (node (ref "U8") (pin "3") (pinfunction "A1_3") (pintype "unspecified"))
    )
    (net (code "41") (name "Q2") (class "Default")
      (node (ref "LED3") (pin "1") (pinfunction "A_1") (pintype "unspecified"))
      (node (ref "U5") (pin "6") (pinfunction "3Q_6") (pintype "unspecified"))
      (node (ref "U8") (pin "4") (pinfunction "A2_4") (pintype "unspecified"))
    )
    (net (code "42") (name "Q3") (class "Default")
      (node (ref "LED4") (pin "1") (pinfunction "A_1") (pintype "unspecified"))
      (node (ref "U5") (pin "9") (pinfunction "4Q_9") (pintype "unspecified"))
      (node (ref "U8") (pin "5") (pinfunction "A3_5") (pintype "unspecified"))
    )
    (net (code "43") (name "Q4") (class "Default")
      (node (ref "LED5") (pin "1") (pinfunction "A_1") (pintype "unspecified"))
      (node (ref "U5") (pin "12") (pinfunction "5Q_12") (pintype "unspecified"))
      (node (ref "U8") (pin "6") (pinfunction "A4_6") (pintype "unspecified"))
    )
    (net (code "44") (name "Q5") (class "Default")
      (node (ref "LED6") (pin "1") (pinfunction "A_1") (pintype "unspecified"))
      (node (ref "U5") (pin "15") (pinfunction "6Q_15") (pintype "unspecified"))
      (node (ref "U8") (pin "7") (pinfunction "A5_7") (pintype "unspecified"))
    )
    (net (code "45") (name "Q6") (class "Default")
      (node (ref "LED7") (pin "1") (pinfunction "A_1") (pintype "unspecified"))
      (node (ref "U5") (pin "16") (pinfunction "7Q_16") (pintype "unspecified"))
      (node (ref "U8") (pin "8") (pinfunction "A6_8") (pintype "unspecified"))
    )
    (net (code "46") (name "Q7") (class "Default")
      (node (ref "LED8") (pin "1") (pinfunction "A_1") (pintype "unspecified"))
      (node (ref "U5") (pin "19") (pinfunction "8Q_19") (pintype "unspecified"))
      (node (ref "U8") (pin "9") (pinfunction "A7_9") (pintype "unspecified"))
    )
    (net (code "47") (name "Q8") (class "Default")
      (node (ref "LED9") (pin "1") (pinfunction "A_1") (pintype "unspecified"))
      (node (ref "U6") (pin "2") (pinfunction "1Q_2") (pintype "unspecified"))
      (node (ref "U7") (pin "2") (pinfunction "A0_2") (pintype "unspecified"))
    )
    (net (code "48") (name "Q9") (class "Default")
      (node (ref "LED10") (pin "1") (pinfunction "A_1") (pintype "unspecified"))
      (node (ref "U6") (pin "5") (pinfunction "2Q_5") (pintype "unspecified"))
      (node (ref "U7") (pin "3") (pinfunction "A1_3") (pintype "unspecified"))
    )
    (net (code "49") (name "Q10") (class "Default")
      (node (ref "LED11") (pin "1") (pinfunction "A_1") (pintype "unspecified"))
      (node (ref "U6") (pin "6") (pinfunction "3Q_6") (pintype "unspecified"))
      (node (ref "U7") (pin "4") (pinfunction "A2_4") (pintype "unspecified"))
    )
    (net (code "50") (name "Q11") (class "Default")
      (node (ref "LED12") (pin "1") (pinfunction "A_1") (pintype "unspecified"))
      (node (ref "U6") (pin "9") (pinfunction "4Q_9") (pintype "unspecified"))
      (node (ref "U7") (pin "5") (pinfunction "A3_5") (pintype "unspecified"))
    )
    (net (code "51") (name "Q12") (class "Default")
      (node (ref "LED13") (pin "1") (pinfunction "A_1") (pintype "unspecified"))
      (node (ref "U6") (pin "12") (pinfunction "5Q_12") (pintype "unspecified"))
      (node (ref "U7") (pin "6") (pinfunction "A4_6") (pintype "unspecified"))
    )
    (net (code "52") (name "Q13") (class "Default")
      (node (ref "LED14") (pin "1") (pinfunction "A_1") (pintype "unspecified"))
      (node (ref "U6") (pin "15") (pinfunction "6Q_15") (pintype "unspecified"))
      (node (ref "U7") (pin "7") (pinfunction "A5_7") (pintype "unspecified"))
    )
    (net (code "53") (name "Q14") (class "Default")
      (node (ref "LED15") (pin "1") (pinfunction "A_1") (pintype "unspecified"))
      (node (ref "U6") (pin "16") (pinfunction "7Q_16") (pintype "unspecified"))
      (node (ref "U7") (pin "8") (pinfunction "A6_8") (pintype "unspecified"))
    )
    (net (code "54") (name "Q15") (class "Default")
      (node (ref "LED16") (pin "1") (pinfunction "A_1") (pintype "unspecified"))
      (node (ref "U6") (pin "19") (pinfunction "8Q_19") (pintype "unspecified"))
      (node (ref "U7") (pin "9") (pinfunction "A7_9") (pintype "unspecified"))
    )
    (net (code "55") (name "REG_BUS0") (class "Default")
      (node (ref "H8") (pin "1") (pinfunction "1_1") (pintype "input"))
      (node (ref "U8") (pin "18") (pinfunction "B0_18") (pintype "unspecified"))
    )
    (net (code "56") (name "REG_BUS1") (class "Default")
      (node (ref "H8") (pin "2") (pinfunction "2_2") (pintype "input"))
      (node (ref "U8") (pin "17") (pinfunction "B1_17") (pintype "unspecified"))
    )
    (net (code "57") (name "REG_BUS2") (class "Default")
      (node (ref "H8") (pin "3") (pinfunction "3_3") (pintype "input"))
      (node (ref "U8") (pin "16") (pinfunction "B2_16") (pintype "unspecified"))
    )
    (net (code "58") (name "REG_BUS3") (class "Default")
      (node (ref "H8") (pin "4") (pinfunction "4_4") (pintype "input"))
      (node (ref "U8") (pin "15") (pinfunction "B3_15") (pintype "unspecified"))
    )
    (net (code "59") (name "REG_BUS4") (class "Default")
      (node (ref "H8") (pin "5") (pinfunction "5_5") (pintype "input"))
      (node (ref "U8") (pin "14") (pinfunction "B4_14") (pintype "unspecified"))
    )
    (net (code "60") (name "REG_BUS5") (class "Default")
      (node (ref "H8") (pin "6") (pinfunction "6_6") (pintype "input"))
      (node (ref "U8") (pin "13") (pinfunction "B5_13") (pintype "unspecified"))
    )
    (net (code "61") (name "REG_BUS6") (class "Default")
      (node (ref "H8") (pin "7") (pinfunction "7_7") (pintype "input"))
      (node (ref "U8") (pin "12") (pinfunction "B6_12") (pintype "unspecified"))
    )
    (net (code "62") (name "REG_BUS7") (class "Default")
      (node (ref "H8") (pin "8") (pinfunction "8_8") (pintype "input"))
      (node (ref "U8") (pin "11") (pinfunction "B7_11") (pintype "unspecified"))
    )
    (net (code "63") (name "REG_BUS8") (class "Default")
      (node (ref "H8") (pin "9") (pinfunction "9_9") (pintype "input"))
      (node (ref "U7") (pin "18") (pinfunction "B0_18") (pintype "unspecified"))
    )
    (net (code "64") (name "REG_BUS9") (class "Default")
      (node (ref "H8") (pin "10") (pinfunction "10_10") (pintype "input"))
      (node (ref "U7") (pin "17") (pinfunction "B1_17") (pintype "unspecified"))
    )
    (net (code "65") (name "REG_BUS10") (class "Default")
      (node (ref "H8") (pin "11") (pinfunction "11_11") (pintype "input"))
      (node (ref "U7") (pin "16") (pinfunction "B2_16") (pintype "unspecified"))
    )
    (net (code "66") (name "REG_BUS11") (class "Default")
      (node (ref "H8") (pin "12") (pinfunction "12_12") (pintype "input"))
      (node (ref "U7") (pin "15") (pinfunction "B3_15") (pintype "unspecified"))
    )
    (net (code "67") (name "REG_BUS12") (class "Default")
      (node (ref "H8") (pin "13") (pinfunction "13_13") (pintype "input"))
      (node (ref "U7") (pin "14") (pinfunction "B4_14") (pintype "unspecified"))
    )
    (net (code "68") (name "REG_BUS13") (class "Default")
      (node (ref "H8") (pin "14") (pinfunction "14_14") (pintype "input"))
      (node (ref "U7") (pin "13") (pinfunction "B5_13") (pintype "unspecified"))
    )
    (net (code "69") (name "REG_BUS14") (class "Default")
      (node (ref "H8") (pin "15") (pinfunction "15_15") (pintype "input"))
      (node (ref "U7") (pin "12") (pinfunction "B6_12") (pintype "unspecified"))
    )
    (net (code "70") (name "REG_BUS15") (class "Default")
      (node (ref "H8") (pin "16") (pinfunction "16_16") (pintype "input"))
      (node (ref "U7") (pin "11") (pinfunction "B7_11") (pintype "unspecified"))
    )
    (net (code "71") (name "VCC") (class "Default")
      (node (ref "C1") (pin "1") (pinfunction "1_1") (pintype "input"))
      (node (ref "C2") (pin "1") (pinfunction "1_1") (pintype "input"))
      (node (ref "C3") (pin "1") (pinfunction "1_1") (pintype "input"))
      (node (ref "C4") (pin "1") (pinfunction "1_1") (pintype "input"))
      (node (ref "H1") (pin "1") (pinfunction "1_1") (pintype "input"))
      (node (ref "H1") (pin "2") (pinfunction "2_2") (pintype "input"))
      (node (ref "H1") (pin "3") (pinfunction "3_3") (pintype "input"))
      (node (ref "H1") (pin "4") (pinfunction "4_4") (pintype "input"))
      (node (ref "H1") (pin "5") (pinfunction "5_5") (pintype "input"))
      (node (ref "H1") (pin "6") (pinfunction "6_6") (pintype "input"))
      (node (ref "H6") (pin "1") (pinfunction "1_1") (pintype "unspecified"))
      (node (ref "H6") (pin "2") (pinfunction "2_2") (pintype "unspecified"))
      (node (ref "Q1") (pin "3") (pinfunction "C_3") (pintype "unspecified"))
      (node (ref "U5") (pin "20") (pinfunction "VCC_20") (pintype "unspecified"))
      (node (ref "U6") (pin "20") (pinfunction "VCC_20") (pintype "unspecified"))
      (node (ref "U7") (pin "1") (pinfunction "DIR_1") (pintype "unspecified"))
      (node (ref "U7") (pin "20") (pinfunction "VCC_20") (pintype "unspecified"))
      (node (ref "U8") (pin "1") (pinfunction "DIR_1") (pintype "unspecified"))
      (node (ref "U8") (pin "20") (pinfunction "VCC_20") (pintype "unspecified"))
    )
    (net (code "72") (name "unconnected-(H3-Pad1)") (class "Default")
      (node (ref "H3") (pin "1") (pinfunction "1_1") (pintype "input+no_connect"))
    )
    (net (code "73") (name "unconnected-(H3-Pad2)") (class "Default")
      (node (ref "H3") (pin "2") (pinfunction "2_2") (pintype "input+no_connect"))
    )
    (net (code "74") (name "unconnected-(H3-Pad3)") (class "Default")
      (node (ref "H3") (pin "3") (pinfunction "3_3") (pintype "input+no_connect"))
    )
    (net (code "75") (name "unconnected-(H3-Pad4)") (class "Default")
      (node (ref "H3") (pin "4") (pinfunction "4_4") (pintype "input+no_connect"))
    )
    (net (code "76") (name "unconnected-(H3-Pad5)") (class "Default")
      (node (ref "H3") (pin "5") (pinfunction "5_5") (pintype "input+no_connect"))
    )
    (net (code "77") (name "unconnected-(H3-Pad6)") (class "Default")
      (node (ref "H3") (pin "6") (pinfunction "6_6") (pintype "input+no_connect"))
    )
    (net (code "78") (name "unconnected-(H4-Pad1)") (class "Default")
      (node (ref "H4") (pin "1") (pinfunction "1_1") (pintype "input+no_connect"))
    )
    (net (code "79") (name "unconnected-(H4-Pad2)") (class "Default")
      (node (ref "H4") (pin "2") (pinfunction "2_2") (pintype "input+no_connect"))
    )
    (net (code "80") (name "unconnected-(H4-Pad3)") (class "Default")
      (node (ref "H4") (pin "3") (pinfunction "3_3") (pintype "input+no_connect"))
    )
    (net (code "81") (name "unconnected-(H4-Pad4)") (class "Default")
      (node (ref "H4") (pin "4") (pinfunction "4_4") (pintype "input+no_connect"))
    )
    (net (code "82") (name "unconnected-(H4-Pad5)") (class "Default")
      (node (ref "H4") (pin "5") (pinfunction "5_5") (pintype "input+no_connect"))
    )
    (net (code "83") (name "unconnected-(H4-Pad6)") (class "Default")
      (node (ref "H4") (pin "6") (pinfunction "6_6") (pintype "input+no_connect"))
    )
    (net (code "84") (name "unconnected-(H5-Pad3)") (class "Default")
      (node (ref "H5") (pin "3") (pinfunction "3_3") (pintype "unspecified+no_connect"))
    )
    (net (code "85") (name "unconnected-(J1-Pad2)") (class "Default")
      (node (ref "J1") (pin "2") (pinfunction "2_2") (pintype "bidirectional+no_connect"))
    )
    (net (code "86") (name "unconnected-(J1-Pad3)") (class "Default")
      (node (ref "J1") (pin "3") (pinfunction "3_3") (pintype "bidirectional+no_connect"))
    )
    (net (code "87") (name "unconnected-(J1-PadMH1)") (class "Default")
      (node (ref "J1") (pin "MH1") (pinfunction "MH1_MH1") (pintype "bidirectional+no_connect"))
    )
    (net (code "88") (name "unconnected-(J1-PadMH2)") (class "Default")
      (node (ref "J1") (pin "MH2") (pinfunction "MH2_MH2") (pintype "bidirectional+no_connect"))
    )
    (net (code "89") (name "unconnected-(U1-A0-Pad2)") (class "Default")
      (node (ref "U1") (pin "2") (pinfunction "A0_2") (pintype "input+no_connect"))
    )
    (net (code "90") (name "unconnected-(U1-A1-Pad23)") (class "Default")
      (node (ref "U1") (pin "23") (pinfunction "A1_23") (pintype "input+no_connect"))
    )
    (net (code "91") (name "unconnected-(U1-A2-Pad21)") (class "Default")
      (node (ref "U1") (pin "21") (pinfunction "A2_21") (pintype "input+no_connect"))
    )
    (net (code "92") (name "unconnected-(U1-A3-Pad19)") (class "Default")
      (node (ref "U1") (pin "19") (pinfunction "A3_19") (pintype "input+no_connect"))
    )
    (net (code "93") (name "unconnected-(U1-A=B-Pad14)") (class "Default")
      (node (ref "U1") (pin "14") (pinfunction "A=B_14") (pintype "output+no_connect"))
    )
    (net (code "94") (name "unconnected-(U1-B0-Pad1)") (class "Default")
      (node (ref "U1") (pin "1") (pinfunction "B0_1") (pintype "input+no_connect"))
    )
    (net (code "95") (name "unconnected-(U1-B1-Pad22)") (class "Default")
      (node (ref "U1") (pin "22") (pinfunction "B1_22") (pintype "input+no_connect"))
    )
    (net (code "96") (name "unconnected-(U1-B2-Pad20)") (class "Default")
      (node (ref "U1") (pin "20") (pinfunction "B2_20") (pintype "input+no_connect"))
    )
    (net (code "97") (name "unconnected-(U1-B3-Pad18)") (class "Default")
      (node (ref "U1") (pin "18") (pinfunction "B3_18") (pintype "input+no_connect"))
    )
    (net (code "98") (name "unconnected-(U1-Cn+4-Pad16)") (class "Default")
      (node (ref "U1") (pin "16") (pinfunction "Cn+4_16") (pintype "output+no_connect"))
    )
    (net (code "99") (name "unconnected-(U1-Cn-Pad7)") (class "Default")
      (node (ref "U1") (pin "7") (pinfunction "Cn_7") (pintype "input+no_connect"))
    )
    (net (code "100") (name "unconnected-(U1-F0-Pad9)") (class "Default")
      (node (ref "U1") (pin "9") (pinfunction "F0_9") (pintype "output+no_connect"))
    )
    (net (code "101") (name "unconnected-(U1-F1-Pad10)") (class "Default")
      (node (ref "U1") (pin "10") (pinfunction "F1_10") (pintype "output+no_connect"))
    )
    (net (code "102") (name "unconnected-(U1-F2-Pad11)") (class "Default")
      (node (ref "U1") (pin "11") (pinfunction "F2_11") (pintype "output+no_connect"))
    )
    (net (code "103") (name "unconnected-(U1-F3-Pad13)") (class "Default")
      (node (ref "U1") (pin "13") (pinfunction "F3_13") (pintype "output+no_connect"))
    )
    (net (code "104") (name "unconnected-(U1-GND-Pad12)") (class "Default")
      (node (ref "U1") (pin "12") (pinfunction "GND_12") (pintype "bidirectional"))
    )
    (net (code "105") (name "unconnected-(U1-M-Pad8)") (class "Default")
      (node (ref "U1") (pin "8") (pinfunction "M_8") (pintype "input+no_connect"))
    )
    (net (code "106") (name "unconnected-(U1-S0-Pad6)") (class "Default")
      (node (ref "U1") (pin "6") (pinfunction "S0_6") (pintype "input+no_connect"))
    )
    (net (code "107") (name "unconnected-(U1-S1-Pad5)") (class "Default")
      (node (ref "U1") (pin "5") (pinfunction "S1_5") (pintype "input+no_connect"))
    )
    (net (code "108") (name "unconnected-(U1-S2-Pad4)") (class "Default")
      (node (ref "U1") (pin "4") (pinfunction "S2_4") (pintype "input+no_connect"))
    )
    (net (code "109") (name "unconnected-(U1-S3-Pad3)") (class "Default")
      (node (ref "U1") (pin "3") (pinfunction "S3_3") (pintype "input+no_connect"))
    )
    (net (code "110") (name "unconnected-(U1-VCC-Pad24)") (class "Default")
      (node (ref "U1") (pin "24") (pinfunction "VCC_24") (pintype "bidirectional"))
    )
    (net (code "111") (name "unconnected-(U1-X-Pad15)") (class "Default")
      (node (ref "U1") (pin "15") (pinfunction "X_15") (pintype "output+no_connect"))
    )
    (net (code "112") (name "unconnected-(U1-Y-Pad17)") (class "Default")
      (node (ref "U1") (pin "17") (pinfunction "Y_17") (pintype "output+no_connect"))
    )
    (net (code "113") (name "unconnected-(U2-A0-Pad2)") (class "Default")
      (node (ref "U2") (pin "2") (pinfunction "A0_2") (pintype "input+no_connect"))
    )
    (net (code "114") (name "unconnected-(U2-A1-Pad23)") (class "Default")
      (node (ref "U2") (pin "23") (pinfunction "A1_23") (pintype "input+no_connect"))
    )
    (net (code "115") (name "unconnected-(U2-A2-Pad21)") (class "Default")
      (node (ref "U2") (pin "21") (pinfunction "A2_21") (pintype "input+no_connect"))
    )
    (net (code "116") (name "unconnected-(U2-A3-Pad19)") (class "Default")
      (node (ref "U2") (pin "19") (pinfunction "A3_19") (pintype "input+no_connect"))
    )
    (net (code "117") (name "unconnected-(U2-A=B-Pad14)") (class "Default")
      (node (ref "U2") (pin "14") (pinfunction "A=B_14") (pintype "output+no_connect"))
    )
    (net (code "118") (name "unconnected-(U2-B0-Pad1)") (class "Default")
      (node (ref "U2") (pin "1") (pinfunction "B0_1") (pintype "input+no_connect"))
    )
    (net (code "119") (name "unconnected-(U2-B1-Pad22)") (class "Default")
      (node (ref "U2") (pin "22") (pinfunction "B1_22") (pintype "input+no_connect"))
    )
    (net (code "120") (name "unconnected-(U2-B2-Pad20)") (class "Default")
      (node (ref "U2") (pin "20") (pinfunction "B2_20") (pintype "input+no_connect"))
    )
    (net (code "121") (name "unconnected-(U2-B3-Pad18)") (class "Default")
      (node (ref "U2") (pin "18") (pinfunction "B3_18") (pintype "input+no_connect"))
    )
    (net (code "122") (name "unconnected-(U2-Cn+4-Pad16)") (class "Default")
      (node (ref "U2") (pin "16") (pinfunction "Cn+4_16") (pintype "output+no_connect"))
    )
    (net (code "123") (name "unconnected-(U2-Cn-Pad7)") (class "Default")
      (node (ref "U2") (pin "7") (pinfunction "Cn_7") (pintype "input+no_connect"))
    )
    (net (code "124") (name "unconnected-(U2-F0-Pad9)") (class "Default")
      (node (ref "U2") (pin "9") (pinfunction "F0_9") (pintype "output+no_connect"))
    )
    (net (code "125") (name "unconnected-(U2-F1-Pad10)") (class "Default")
      (node (ref "U2") (pin "10") (pinfunction "F1_10") (pintype "output+no_connect"))
    )
    (net (code "126") (name "unconnected-(U2-F2-Pad11)") (class "Default")
      (node (ref "U2") (pin "11") (pinfunction "F2_11") (pintype "output+no_connect"))
    )
    (net (code "127") (name "unconnected-(U2-F3-Pad13)") (class "Default")
      (node (ref "U2") (pin "13") (pinfunction "F3_13") (pintype "output+no_connect"))
    )
    (net (code "128") (name "unconnected-(U2-GND-Pad12)") (class "Default")
      (node (ref "U2") (pin "12") (pinfunction "GND_12") (pintype "bidirectional"))
    )
    (net (code "129") (name "unconnected-(U2-M-Pad8)") (class "Default")
      (node (ref "U2") (pin "8") (pinfunction "M_8") (pintype "input+no_connect"))
    )
    (net (code "130") (name "unconnected-(U2-S0-Pad6)") (class "Default")
      (node (ref "U2") (pin "6") (pinfunction "S0_6") (pintype "input+no_connect"))
    )
    (net (code "131") (name "unconnected-(U2-S1-Pad5)") (class "Default")
      (node (ref "U2") (pin "5") (pinfunction "S1_5") (pintype "input+no_connect"))
    )
    (net (code "132") (name "unconnected-(U2-S2-Pad4)") (class "Default")
      (node (ref "U2") (pin "4") (pinfunction "S2_4") (pintype "input+no_connect"))
    )
    (net (code "133") (name "unconnected-(U2-S3-Pad3)") (class "Default")
      (node (ref "U2") (pin "3") (pinfunction "S3_3") (pintype "input+no_connect"))
    )
    (net (code "134") (name "unconnected-(U2-VCC-Pad24)") (class "Default")
      (node (ref "U2") (pin "24") (pinfunction "VCC_24") (pintype "bidirectional"))
    )
    (net (code "135") (name "unconnected-(U2-X-Pad15)") (class "Default")
      (node (ref "U2") (pin "15") (pinfunction "X_15") (pintype "output+no_connect"))
    )
    (net (code "136") (name "unconnected-(U2-Y-Pad17)") (class "Default")
      (node (ref "U2") (pin "17") (pinfunction "Y_17") (pintype "output+no_connect"))
    )
    (net (code "137") (name "unconnected-(U3-A0-Pad2)") (class "Default")
      (node (ref "U3") (pin "2") (pinfunction "A0_2") (pintype "input+no_connect"))
    )
    (net (code "138") (name "unconnected-(U3-A1-Pad23)") (class "Default")
      (node (ref "U3") (pin "23") (pinfunction "A1_23") (pintype "input+no_connect"))
    )
    (net (code "139") (name "unconnected-(U3-A2-Pad21)") (class "Default")
      (node (ref "U3") (pin "21") (pinfunction "A2_21") (pintype "input+no_connect"))
    )
    (net (code "140") (name "unconnected-(U3-A3-Pad19)") (class "Default")
      (node (ref "U3") (pin "19") (pinfunction "A3_19") (pintype "input+no_connect"))
    )
    (net (code "141") (name "unconnected-(U3-A=B-Pad14)") (class "Default")
      (node (ref "U3") (pin "14") (pinfunction "A=B_14") (pintype "output+no_connect"))
    )
    (net (code "142") (name "unconnected-(U3-B0-Pad1)") (class "Default")
      (node (ref "U3") (pin "1") (pinfunction "B0_1") (pintype "input+no_connect"))
    )
    (net (code "143") (name "unconnected-(U3-B1-Pad22)") (class "Default")
      (node (ref "U3") (pin "22") (pinfunction "B1_22") (pintype "input+no_connect"))
    )
    (net (code "144") (name "unconnected-(U3-B2-Pad20)") (class "Default")
      (node (ref "U3") (pin "20") (pinfunction "B2_20") (pintype "input+no_connect"))
    )
    (net (code "145") (name "unconnected-(U3-B3-Pad18)") (class "Default")
      (node (ref "U3") (pin "18") (pinfunction "B3_18") (pintype "input+no_connect"))
    )
    (net (code "146") (name "unconnected-(U3-Cn+4-Pad16)") (class "Default")
      (node (ref "U3") (pin "16") (pinfunction "Cn+4_16") (pintype "output+no_connect"))
    )
    (net (code "147") (name "unconnected-(U3-Cn-Pad7)") (class "Default")
      (node (ref "U3") (pin "7") (pinfunction "Cn_7") (pintype "input+no_connect"))
    )
    (net (code "148") (name "unconnected-(U3-F0-Pad9)") (class "Default")
      (node (ref "U3") (pin "9") (pinfunction "F0_9") (pintype "output+no_connect"))
    )
    (net (code "149") (name "unconnected-(U3-F1-Pad10)") (class "Default")
      (node (ref "U3") (pin "10") (pinfunction "F1_10") (pintype "output+no_connect"))
    )
    (net (code "150") (name "unconnected-(U3-F2-Pad11)") (class "Default")
      (node (ref "U3") (pin "11") (pinfunction "F2_11") (pintype "output+no_connect"))
    )
    (net (code "151") (name "unconnected-(U3-F3-Pad13)") (class "Default")
      (node (ref "U3") (pin "13") (pinfunction "F3_13") (pintype "output+no_connect"))
    )
    (net (code "152") (name "unconnected-(U3-GND-Pad12)") (class "Default")
      (node (ref "U3") (pin "12") (pinfunction "GND_12") (pintype "bidirectional"))
    )
    (net (code "153") (name "unconnected-(U3-M-Pad8)") (class "Default")
      (node (ref "U3") (pin "8") (pinfunction "M_8") (pintype "input+no_connect"))
    )
    (net (code "154") (name "unconnected-(U3-S0-Pad6)") (class "Default")
      (node (ref "U3") (pin "6") (pinfunction "S0_6") (pintype "input+no_connect"))
    )
    (net (code "155") (name "unconnected-(U3-S1-Pad5)") (class "Default")
      (node (ref "U3") (pin "5") (pinfunction "S1_5") (pintype "input+no_connect"))
    )
    (net (code "156") (name "unconnected-(U3-S2-Pad4)") (class "Default")
      (node (ref "U3") (pin "4") (pinfunction "S2_4") (pintype "input+no_connect"))
    )
    (net (code "157") (name "unconnected-(U3-S3-Pad3)") (class "Default")
      (node (ref "U3") (pin "3") (pinfunction "S3_3") (pintype "input+no_connect"))
    )
    (net (code "158") (name "unconnected-(U3-VCC-Pad24)") (class "Default")
      (node (ref "U3") (pin "24") (pinfunction "VCC_24") (pintype "bidirectional"))
    )
    (net (code "159") (name "unconnected-(U3-X-Pad15)") (class "Default")
      (node (ref "U3") (pin "15") (pinfunction "X_15") (pintype "output+no_connect"))
    )
    (net (code "160") (name "unconnected-(U3-Y-Pad17)") (class "Default")
      (node (ref "U3") (pin "17") (pinfunction "Y_17") (pintype "output+no_connect"))
    )
    (net (code "161") (name "unconnected-(U4-A0-Pad2)") (class "Default")
      (node (ref "U4") (pin "2") (pinfunction "A0_2") (pintype "input+no_connect"))
    )
    (net (code "162") (name "unconnected-(U4-A1-Pad23)") (class "Default")
      (node (ref "U4") (pin "23") (pinfunction "A1_23") (pintype "input+no_connect"))
    )
    (net (code "163") (name "unconnected-(U4-A2-Pad21)") (class "Default")
      (node (ref "U4") (pin "21") (pinfunction "A2_21") (pintype "input+no_connect"))
    )
    (net (code "164") (name "unconnected-(U4-A3-Pad19)") (class "Default")
      (node (ref "U4") (pin "19") (pinfunction "A3_19") (pintype "input+no_connect"))
    )
    (net (code "165") (name "unconnected-(U4-A=B-Pad14)") (class "Default")
      (node (ref "U4") (pin "14") (pinfunction "A=B_14") (pintype "output+no_connect"))
    )
    (net (code "166") (name "unconnected-(U4-B0-Pad1)") (class "Default")
      (node (ref "U4") (pin "1") (pinfunction "B0_1") (pintype "input+no_connect"))
    )
    (net (code "167") (name "unconnected-(U4-B1-Pad22)") (class "Default")
      (node (ref "U4") (pin "22") (pinfunction "B1_22") (pintype "input+no_connect"))
    )
    (net (code "168") (name "unconnected-(U4-B2-Pad20)") (class "Default")
      (node (ref "U4") (pin "20") (pinfunction "B2_20") (pintype "input+no_connect"))
    )
    (net (code "169") (name "unconnected-(U4-B3-Pad18)") (class "Default")
      (node (ref "U4") (pin "18") (pinfunction "B3_18") (pintype "input+no_connect"))
    )
    (net (code "170") (name "unconnected-(U4-Cn+4-Pad16)") (class "Default")
      (node (ref "U4") (pin "16") (pinfunction "Cn+4_16") (pintype "output+no_connect"))
    )
    (net (code "171") (name "unconnected-(U4-Cn-Pad7)") (class "Default")
      (node (ref "U4") (pin "7") (pinfunction "Cn_7") (pintype "input+no_connect"))
    )
    (net (code "172") (name "unconnected-(U4-F0-Pad9)") (class "Default")
      (node (ref "U4") (pin "9") (pinfunction "F0_9") (pintype "output+no_connect"))
    )
    (net (code "173") (name "unconnected-(U4-F1-Pad10)") (class "Default")
      (node (ref "U4") (pin "10") (pinfunction "F1_10") (pintype "output+no_connect"))
    )
    (net (code "174") (name "unconnected-(U4-F2-Pad11)") (class "Default")
      (node (ref "U4") (pin "11") (pinfunction "F2_11") (pintype "output+no_connect"))
    )
    (net (code "175") (name "unconnected-(U4-F3-Pad13)") (class "Default")
      (node (ref "U4") (pin "13") (pinfunction "F3_13") (pintype "output+no_connect"))
    )
    (net (code "176") (name "unconnected-(U4-GND-Pad12)") (class "Default")
      (node (ref "U4") (pin "12") (pinfunction "GND_12") (pintype "bidirectional"))
    )
    (net (code "177") (name "unconnected-(U4-M-Pad8)") (class "Default")
      (node (ref "U4") (pin "8") (pinfunction "M_8") (pintype "input+no_connect"))
    )
    (net (code "178") (name "unconnected-(U4-S0-Pad6)") (class "Default")
      (node (ref "U4") (pin "6") (pinfunction "S0_6") (pintype "input+no_connect"))
    )
    (net (code "179") (name "unconnected-(U4-S1-Pad5)") (class "Default")
      (node (ref "U4") (pin "5") (pinfunction "S1_5") (pintype "input+no_connect"))
    )
    (net (code "180") (name "unconnected-(U4-S2-Pad4)") (class "Default")
      (node (ref "U4") (pin "4") (pinfunction "S2_4") (pintype "input+no_connect"))
    )
    (net (code "181") (name "unconnected-(U4-S3-Pad3)") (class "Default")
      (node (ref "U4") (pin "3") (pinfunction "S3_3") (pintype "input+no_connect"))
    )
    (net (code "182") (name "unconnected-(U4-VCC-Pad24)") (class "Default")
      (node (ref "U4") (pin "24") (pinfunction "VCC_24") (pintype "bidirectional"))
    )
    (net (code "183") (name "unconnected-(U4-X-Pad15)") (class "Default")
      (node (ref "U4") (pin "15") (pinfunction "X_15") (pintype "output+no_connect"))
    )
    (net (code "184") (name "unconnected-(U4-Y-Pad17)") (class "Default")
      (node (ref "U4") (pin "17") (pinfunction "Y_17") (pintype "output+no_connect"))
    )
    (net (code "185") (name "{slash}EN") (class "Default")
      (node (ref "H5") (pin "1") (pinfunction "1_1") (pintype "unspecified"))
      (node (ref "U5") (pin "1") (pinfunction "CLKEN#_1") (pintype "unspecified"))
      (node (ref "U6") (pin "1") (pinfunction "CLKEN#_1") (pintype "unspecified"))
    )
    (net (code "186") (name "{slash}OE") (class "Default")
      (node (ref "H5") (pin "2") (pinfunction "2_2") (pintype "unspecified"))
      (node (ref "U7") (pin "19") (pinfunction "OE_19") (pintype "unspecified"))
      (node (ref "U8") (pin "19") (pinfunction "OE_19") (pintype "unspecified"))
    )
  )
)
